# Controller_Board.net
KiCad netlist of a schematic drawn in EAGLE
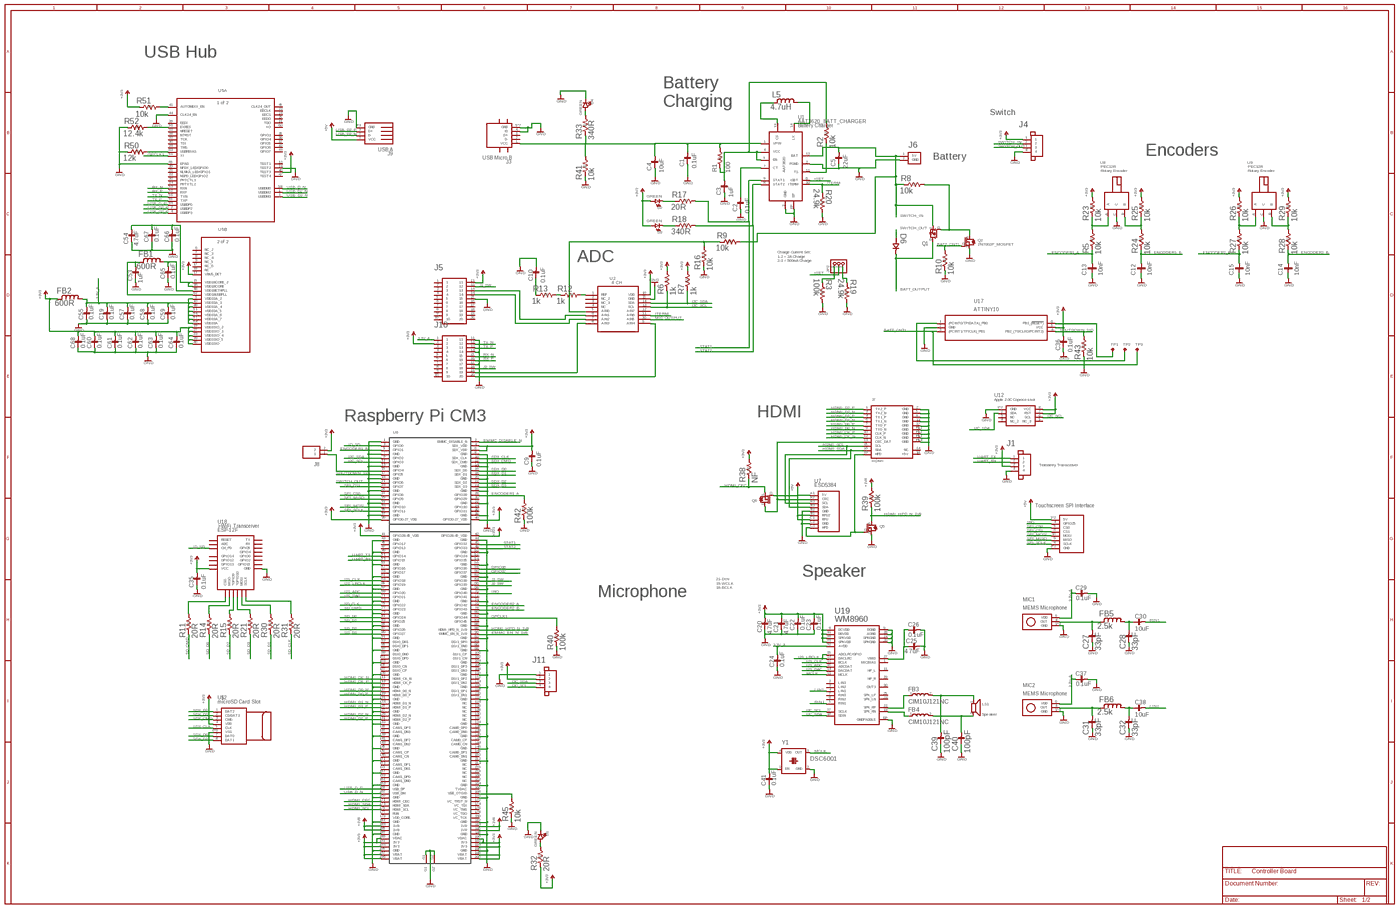
[diagram p0: schematic, sheet 1, overview]
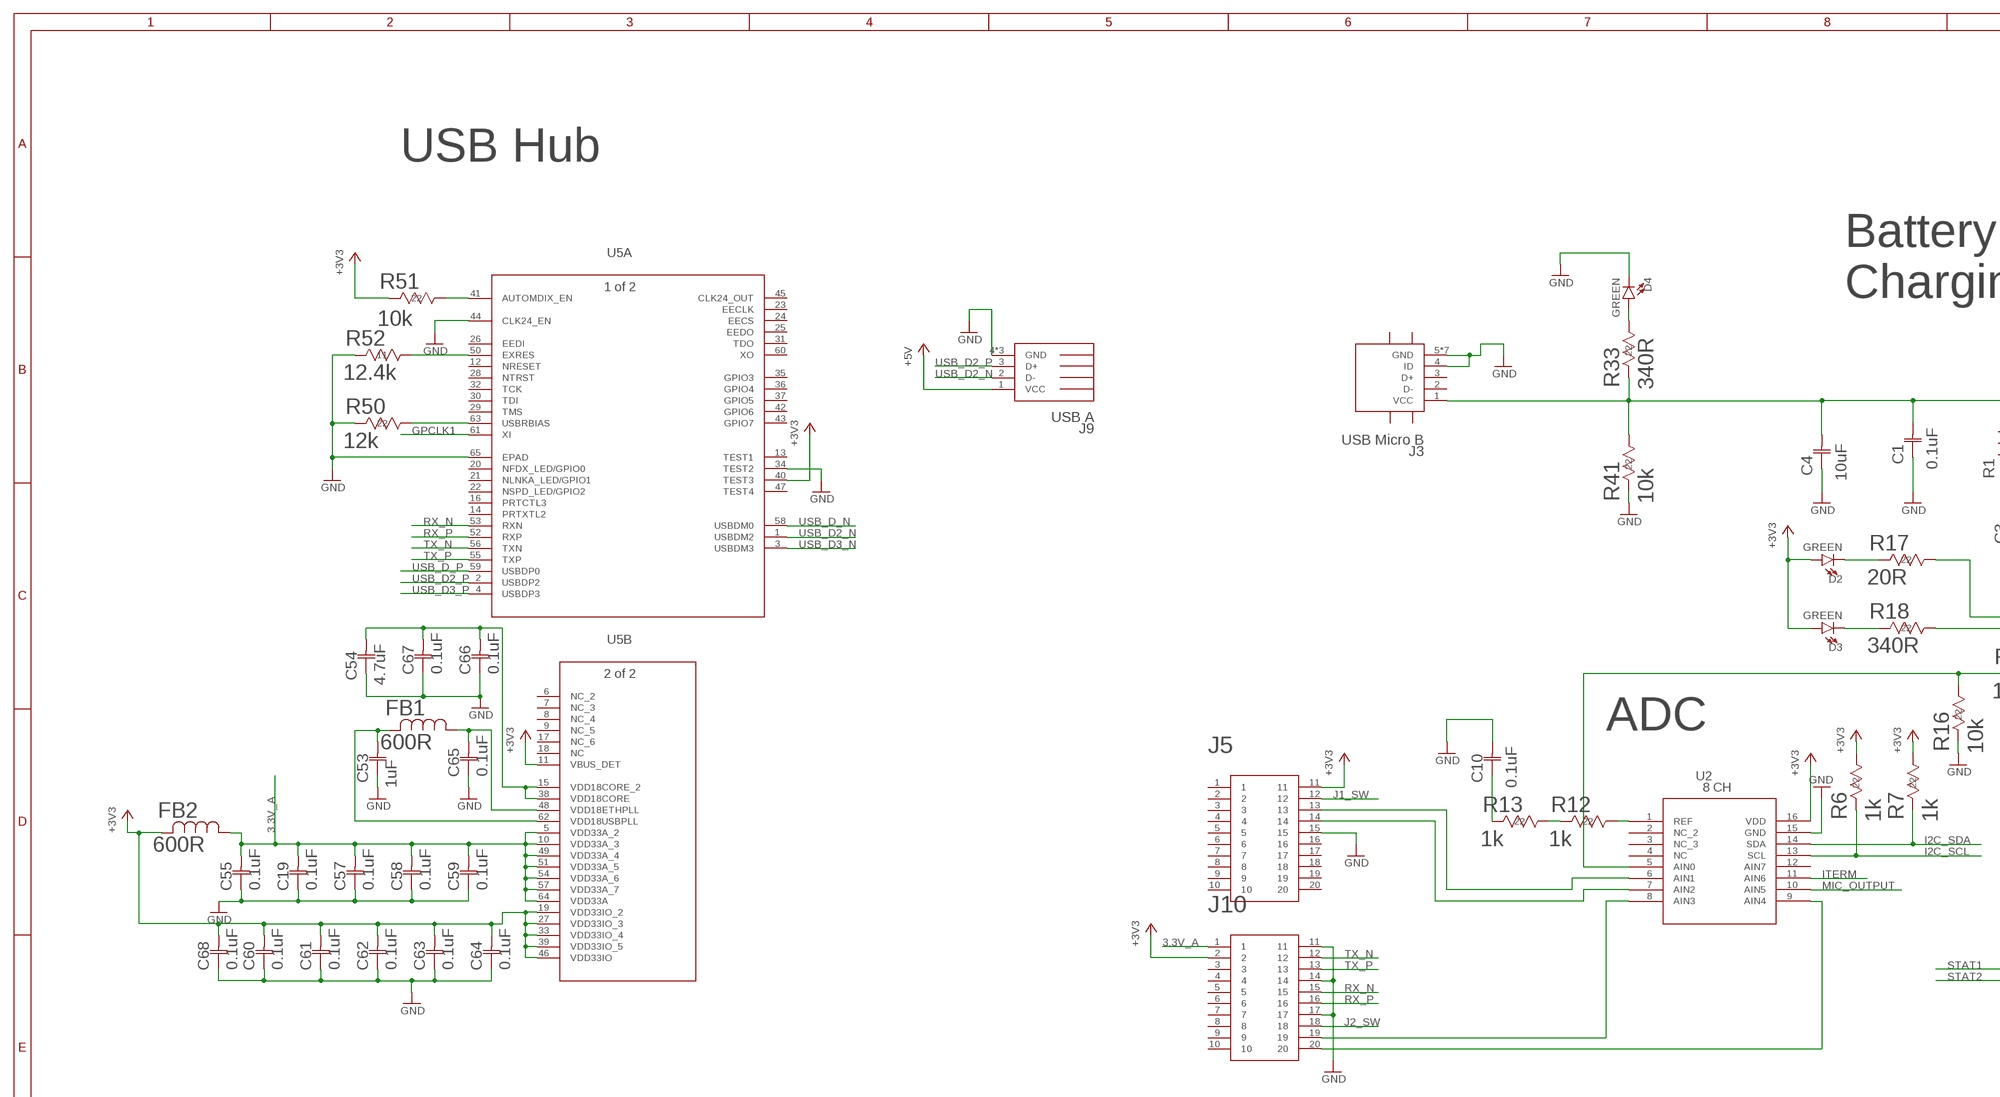
[diagram p1: schematic, sheet 1, part 1 of 4]
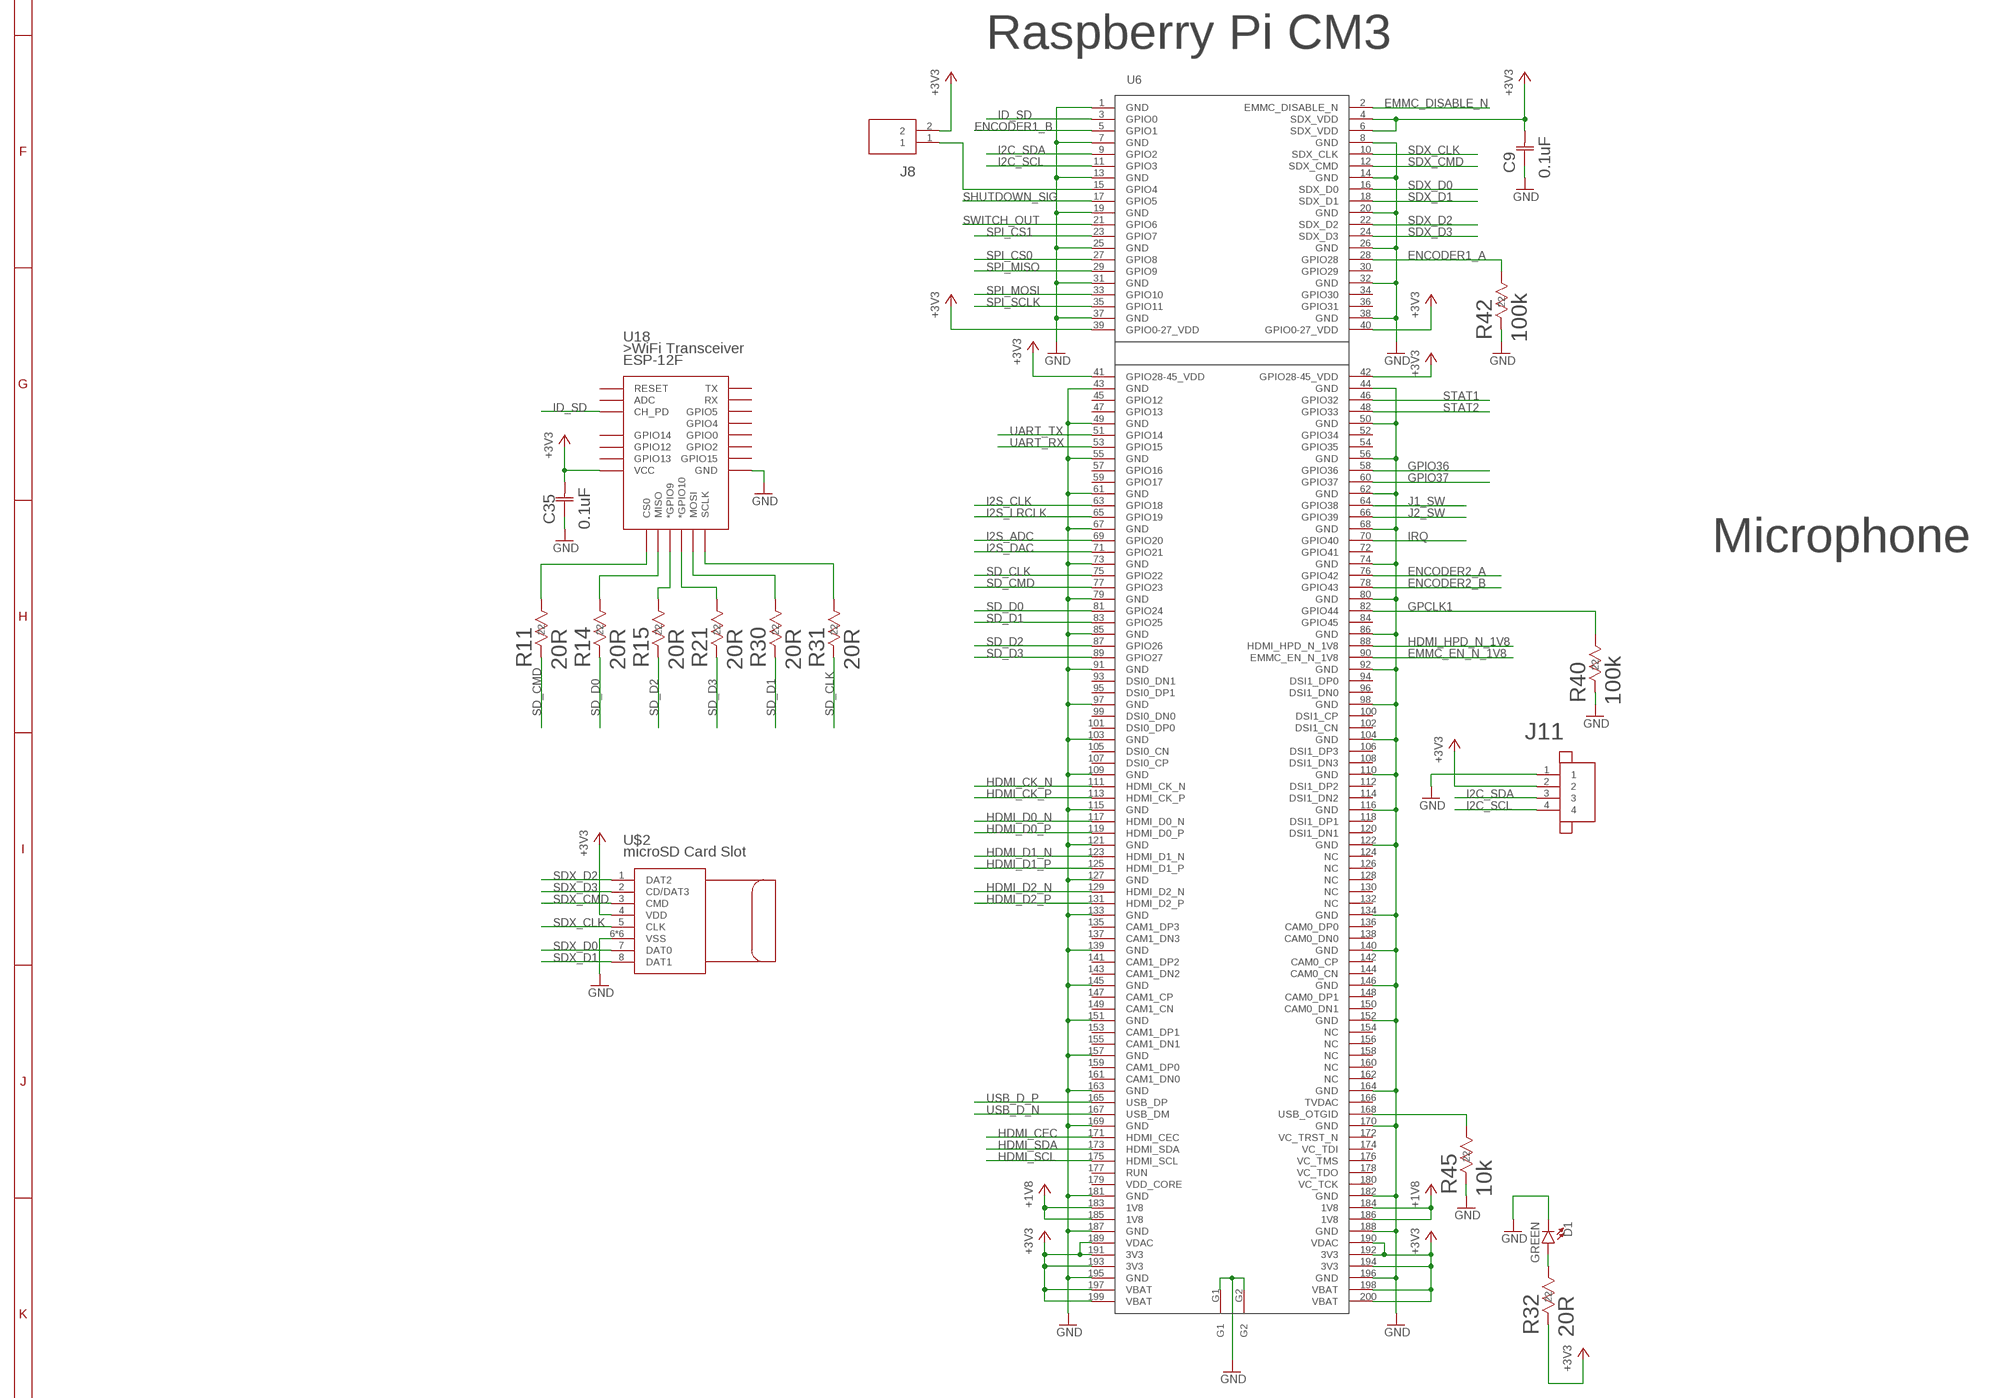
[diagram p2: schematic, sheet 1, part 2 of 4]
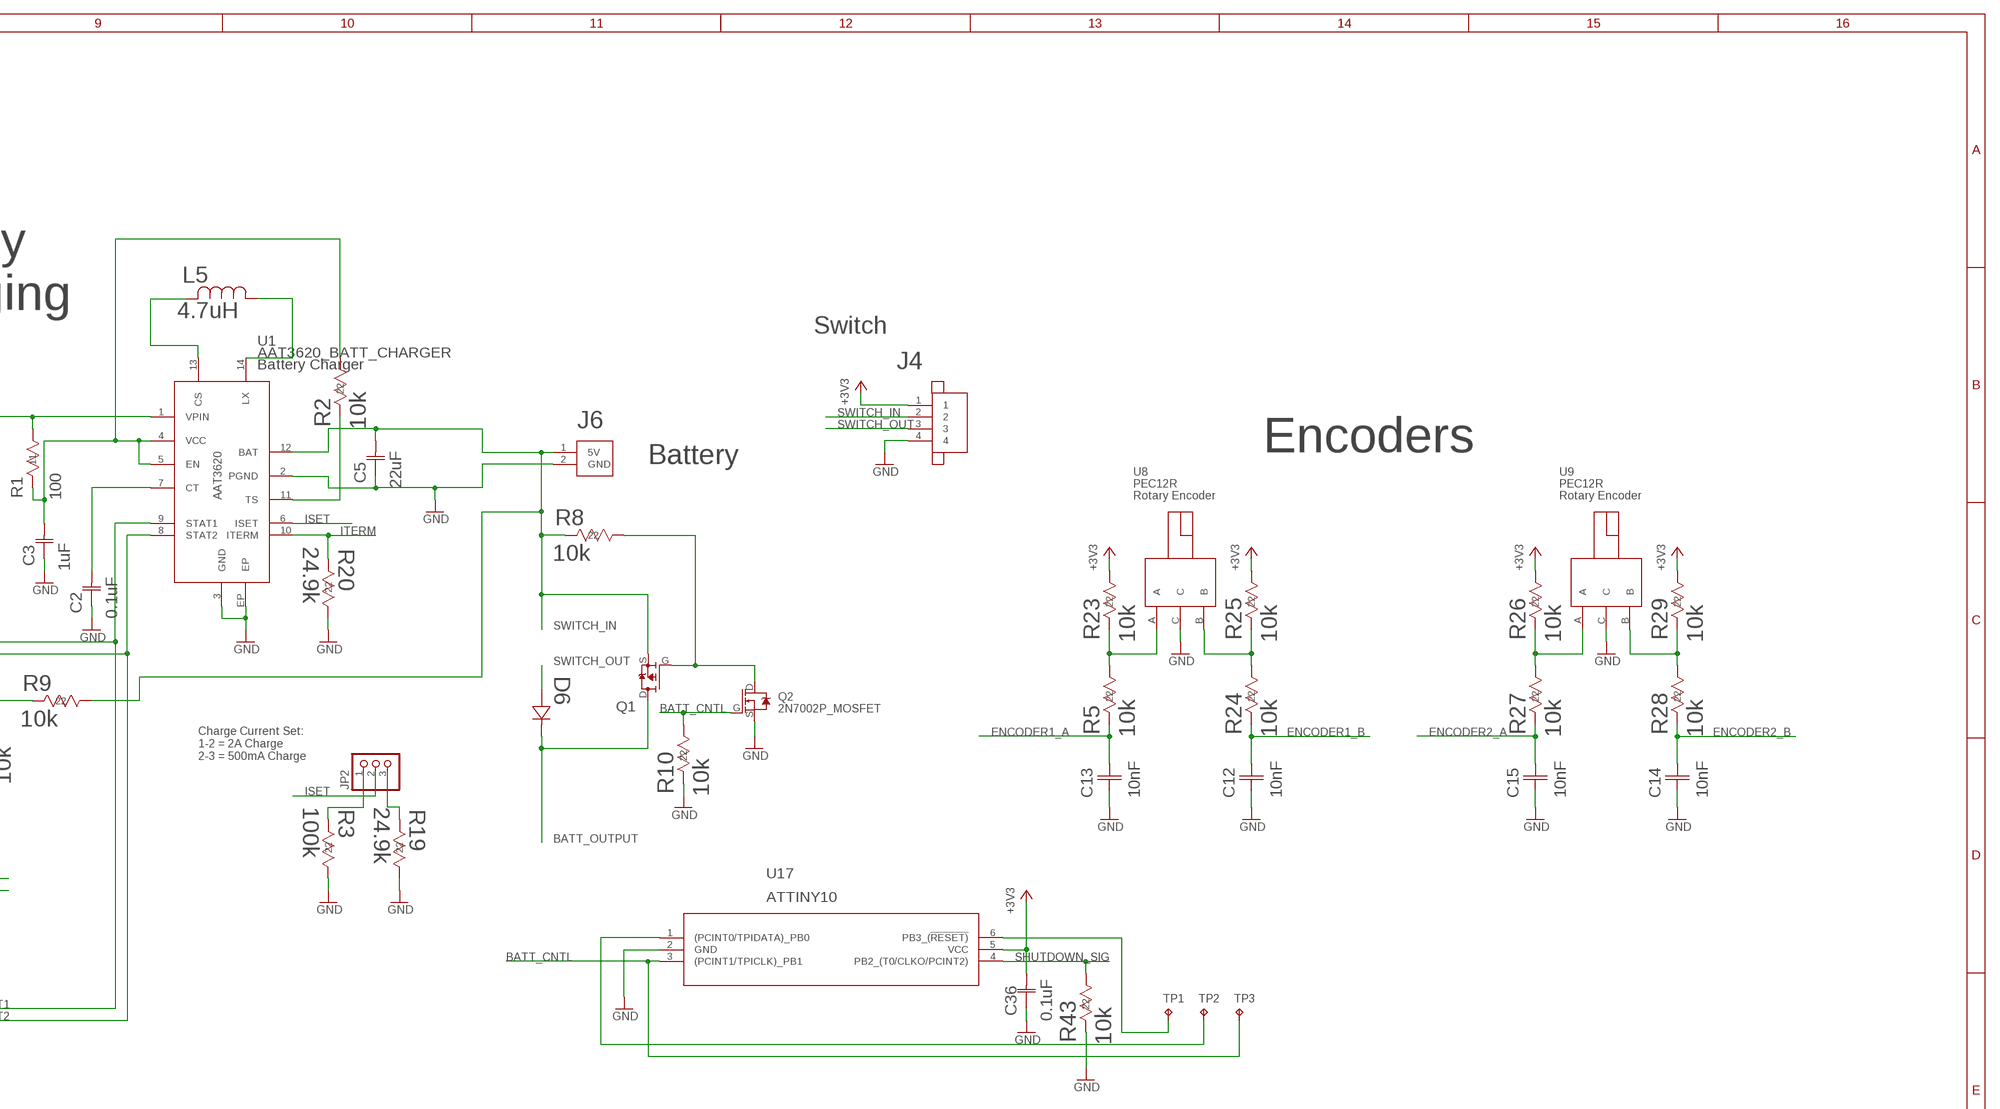
[diagram p3: schematic, sheet 1, part 3 of 4]
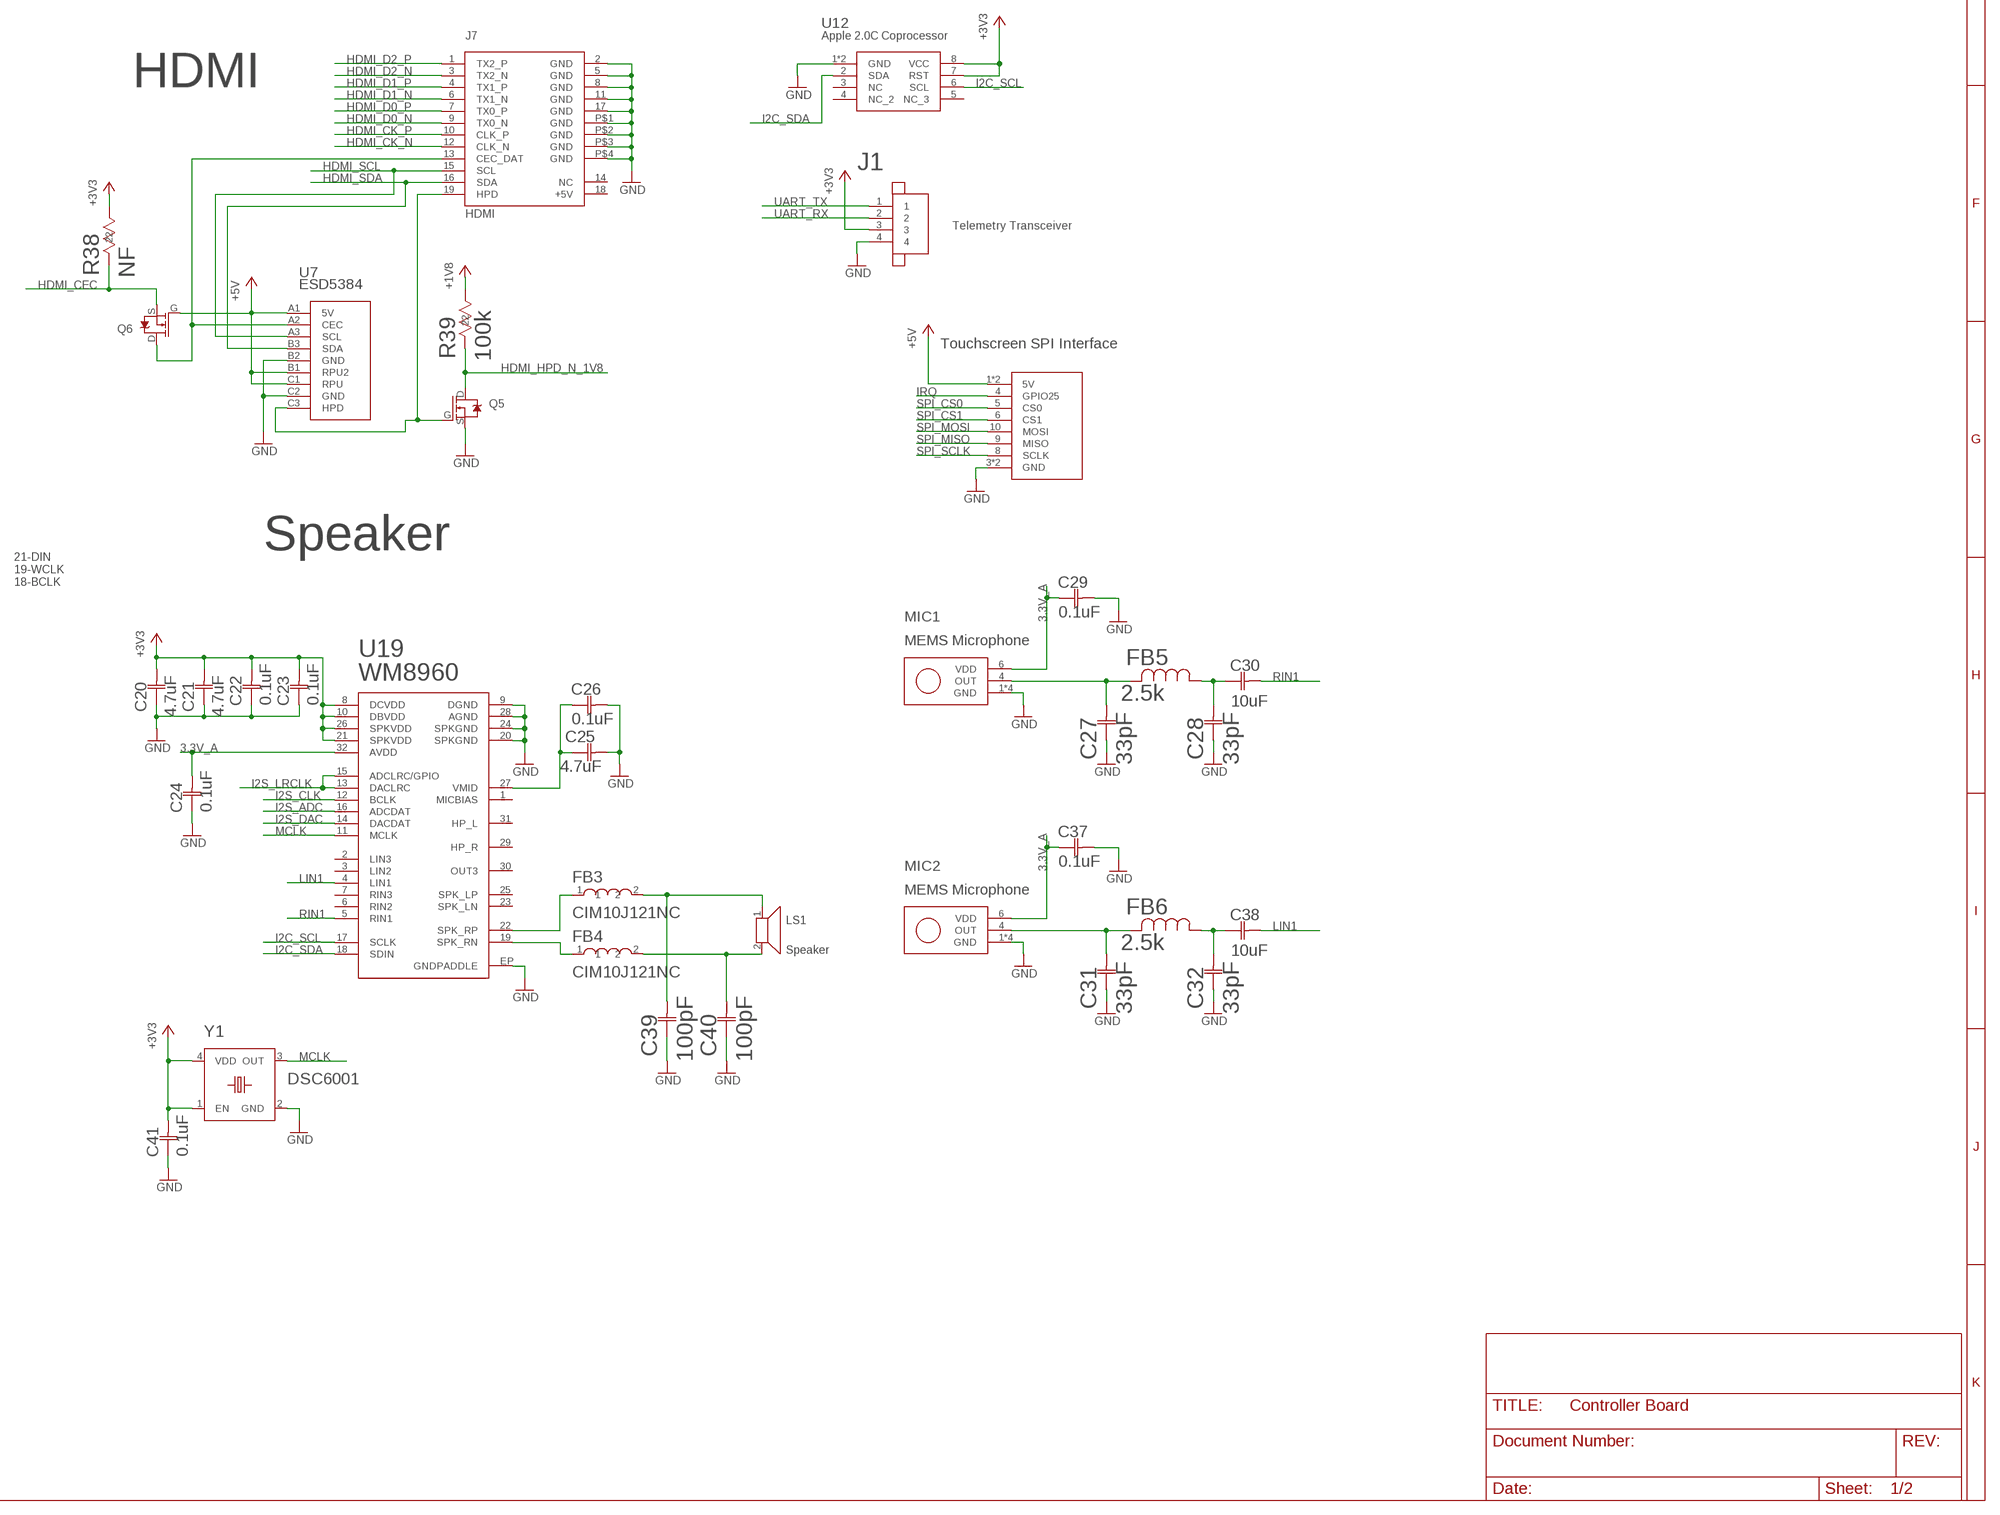
[diagram p4: schematic, sheet 1, part 4 of 4]
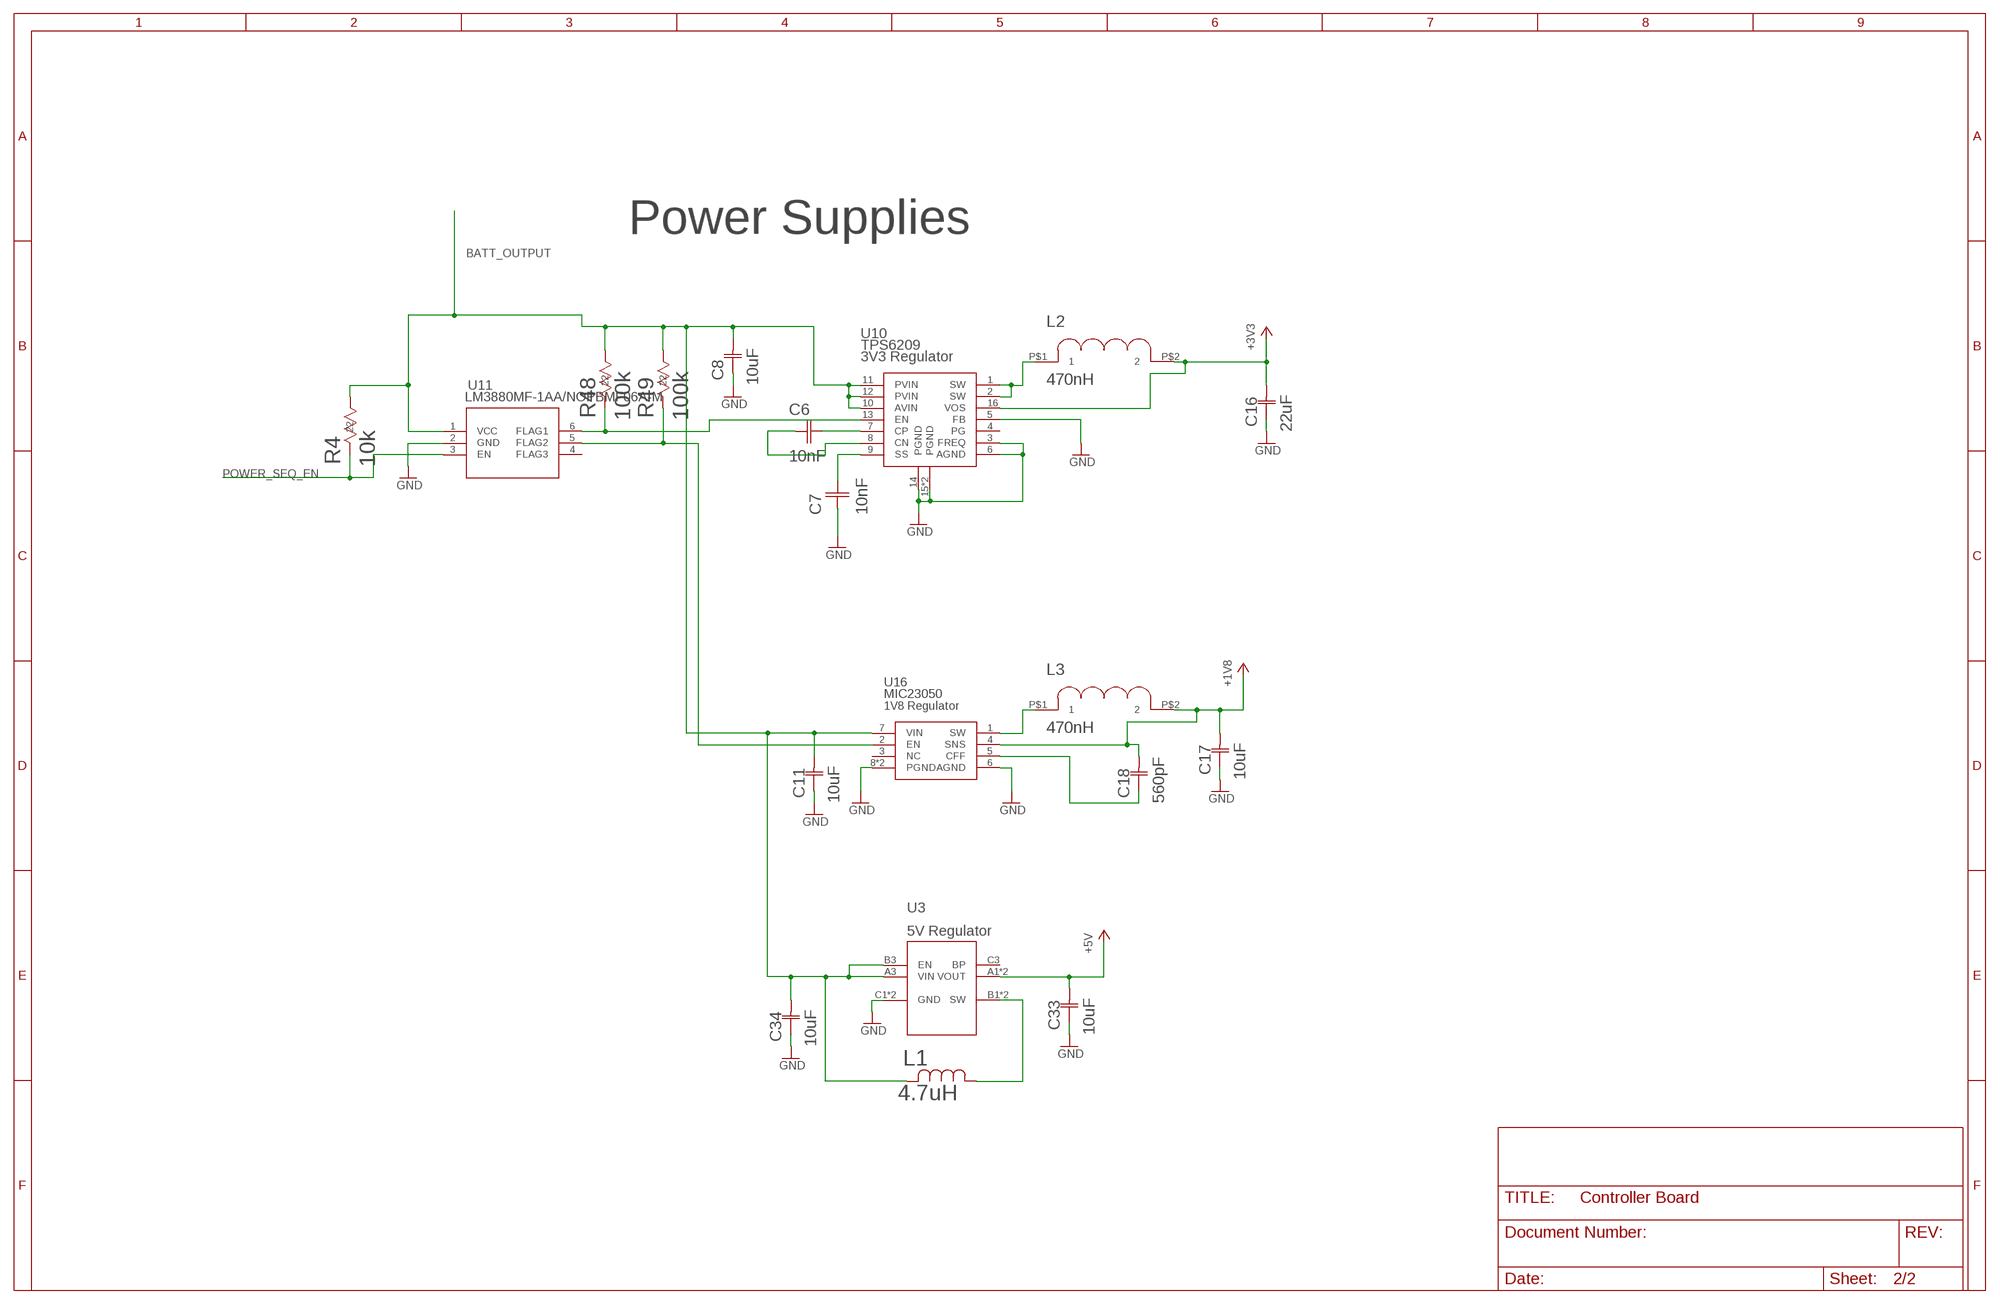
[diagram p5: schematic, sheet 2]

(export (version "E")
  (design (tool "Eeschema 10.0.6"))
  (components
    (comp (ref "C6")
      (value "10nF")
      (footprint "eagle-import:0603_CAPACITOR")
      (libsource (lib "eagle-import") (part "10NF_CAPACITOR"))
    )
    (comp (ref "C7")
      (value "10nF")
      (footprint "eagle-import:0603_CAPACITOR")
      (libsource (lib "eagle-import") (part "10NF_CAPACITOR"))
    )
    (comp (ref "C8")
      (value "10uF")
      (footprint "eagle-import:G-21")
      (fields
        (field (name "MANUFACTURER_PART_NUMBER") "GRM21BR60J106ME19L")
        (field (name "COPYRIGHT") "Copyright C 2015 Accelerated Designs. All rights reserved")
      )
      (libsource (lib "eagle-import") (part "Controller Board_178037_GRM21BR60J106ME19L"))
    )
    (comp (ref "C11")
      (value "10uF")
      (footprint "eagle-import:G-21")
      (fields
        (field (name "MANUFACTURER_PART_NUMBER") "GRM21BR60J106ME19L")
        (field (name "COPYRIGHT") "Copyright C 2015 Accelerated Designs. All rights reserved")
      )
      (libsource (lib "eagle-import") (part "Controller Board_178037_GRM21BR60J106ME19L"))
    )
    (comp (ref "C16")
      (value "22uF")
      (footprint "eagle-import:G-21")
      (fields
        (field (name "MANUFACTURER_PART_NUMBER") "GRM21BR60J226ME39L")
        (field (name "COPYRIGHT") "Copyright C 2015 Accelerated Designs. All rights reserved")
      )
      (libsource (lib "eagle-import") (part "GRM21BR60J226ME39L"))
    )
    (comp (ref "C17")
      (value "10uF")
      (footprint "eagle-import:G-21")
      (fields
        (field (name "MANUFACTURER_PART_NUMBER") "GRM21BR60J106ME19L")
        (field (name "COPYRIGHT") "Copyright C 2015 Accelerated Designs. All rights reserved")
      )
      (libsource (lib "eagle-import") (part "Controller Board_178037_GRM21BR60J106ME19L"))
    )
    (comp (ref "C18")
      (value "560pF")
      (footprint "eagle-import:CC0402N-M")
      (fields (field (name "MANUFACTURER_PART_NUMBER") "CC0402KRX7R9BB561"))
      (libsource (lib "eagle-import") (part "CC0402KRX7R9BB561CC0402N-M"))
    )
    (comp (ref "C33")
      (value "10uF")
      (footprint "eagle-import:G-21")
      (fields
        (field (name "MANUFACTURER_PART_NUMBER") "GRM21BR60J106ME19L")
        (field (name "COPYRIGHT") "Copyright C 2015 Accelerated Designs. All rights reserved")
      )
      (libsource (lib "eagle-import") (part "Controller Board_178037_GRM21BR60J106ME19L"))
    )
    (comp (ref "C34")
      (value "10uF")
      (footprint "eagle-import:G-21")
      (fields
        (field (name "MANUFACTURER_PART_NUMBER") "GRM21BR60J106ME19L")
        (field (name "COPYRIGHT") "Copyright C 2015 Accelerated Designs. All rights reserved")
      )
      (libsource (lib "eagle-import") (part "Controller Board_178037_GRM21BR60J106ME19L"))
    )
    (comp (ref "L1")
      (value "4.7uH")
      (footprint "eagle-import:1008")
      (libsource (lib "eagle-import") (part "DFE252012P-4R7M=P2{dblquote}"))
    )
    (comp (ref "L2")
      (value "470nH")
      (footprint "eagle-import:470NH_INDUCTOR")
      (libsource (lib "eagle-import") (part "470NH_INDUCTOR"))
    )
    (comp (ref "L3")
      (value "470nH")
      (footprint "eagle-import:470NH_INDUCTOR")
      (libsource (lib "eagle-import") (part "470NH_INDUCTOR"))
    )
    (comp (ref "R4")
      (value "10k")
      (footprint "eagle-import:RC0805N")
      (fields
        (field (name "DIGIKEYPARTNUMBER") "P10KDATRND")
        (field (name "MANUFACTURER_PART_NUMBER") "ERA6AEB103V")
        (field (name "TOLERANCE") "0.1%")
        (field (name "COPYRIGHT") "Copyright C 2015 Accelerated Designs. All rights reserved")
      )
      (libsource (lib "eagle-import") (part "Controller Board_178037_ERA-6AEB103V"))
    )
    (comp (ref "R48")
      (value "100k")
      (footprint "eagle-import:RC0603N-M")
      (fields (field (name "MANUFACTURER_PART_NUMBER") "RC0603JR07100KL"))
      (libsource (lib "eagle-import") (part "RC0603JR-07100KLRC0603N-M"))
    )
    (comp (ref "R49")
      (value "100k")
      (footprint "eagle-import:RC0603N-M")
      (fields (field (name "MANUFACTURER_PART_NUMBER") "RC0603JR07100KL"))
      (libsource (lib "eagle-import") (part "RC0603JR-07100KLRC0603N-M"))
    )
    (comp (ref "U3")
      (value "TPS61256YFFR")
      (footprint "eagle-import:YFF9")
      (libsource (lib "eagle-import") (part "TPS61256YFFR"))
    )
    (comp (ref "U10")
      (value "TPS6209")
      (footprint "eagle-import:VQFN16")
      (libsource (lib "eagle-import") (part "TPS6209"))
    )
    (comp (ref "U11")
      (value "LM3880MF-1AA/NOPBMF06A-M")
      (footprint "eagle-import:MF06A-M")
      (fields (field (name "MANUFACTURER_PART_NUMBER") "lm3880mf1aaNOPB"))
      (libsource (lib "eagle-import") (part "LM3880MF-1AA/NOPBMF06A-M"))
    )
    (comp (ref "U16")
      (value "MIC23050")
      (footprint "eagle-import:MLF(ML)_8PIN")
      (libsource (lib "eagle-import") (part "MIC23050"))
    )
    (comp (ref "C1")
      (value "0.1uF")
      (footprint "eagle-import:0805")
      (fields
        (field (name "MANUFACTURER_PART_NUMBER") "08055C104KAT2A")
        (field (name "COPYRIGHT") "Copyright C 2015 Accelerated Designs. All rights reserved")
      )
      (libsource (lib "eagle-import") (part "08055C104KAT2A"))
    )
    (comp (ref "C2")
      (value "0.1uF")
      (footprint "eagle-import:0805")
      (fields
        (field (name "MANUFACTURER_PART_NUMBER") "08055C104KAT2A")
        (field (name "COPYRIGHT") "Copyright C 2015 Accelerated Designs. All rights reserved")
      )
      (libsource (lib "eagle-import") (part "08055C104KAT2A"))
    )
    (comp (ref "C3")
      (value "1uF")
      (footprint "eagle-import:YAG_CC0805")
      (fields
        (field (name "MANUFACTURER_PART_NUMBER") "CC0805KKX7R7BB105")
        (field (name "COPYRIGHT") "Copyright C 2015 Accelerated Designs. All rights reserved")
      )
      (libsource (lib "eagle-import") (part "Controller Board_178037_CC0805KKX7R7BB105"))
    )
    (comp (ref "C4")
      (value "10uF")
      (footprint "eagle-import:G-21")
      (fields
        (field (name "MANUFACTURER_PART_NUMBER") "GRM21BR60J106ME19L")
        (field (name "COPYRIGHT") "Copyright C 2015 Accelerated Designs. All rights reserved")
      )
      (libsource (lib "eagle-import") (part "Controller Board_178037_GRM21BR60J106ME19L"))
    )
    (comp (ref "C5")
      (value "22uF")
      (footprint "eagle-import:G-21")
      (fields
        (field (name "MANUFACTURER_PART_NUMBER") "GRM21BR60J226ME39L")
        (field (name "COPYRIGHT") "Copyright C 2015 Accelerated Designs. All rights reserved")
      )
      (libsource (lib "eagle-import") (part "GRM21BR60J226ME39L"))
    )
    (comp (ref "C9")
      (value "0.1uF")
      (footprint "eagle-import:0805")
      (fields
        (field (name "MANUFACTURER_PART_NUMBER") "08055C104KAT2A")
        (field (name "COPYRIGHT") "Copyright C 2015 Accelerated Designs. All rights reserved")
      )
      (libsource (lib "eagle-import") (part "08055C104KAT2A"))
    )
    (comp (ref "C10")
      (value "0.1uF")
      (footprint "eagle-import:0805")
      (fields
        (field (name "MANUFACTURER_PART_NUMBER") "08055C104KAT2A")
        (field (name "COPYRIGHT") "Copyright C 2015 Accelerated Designs. All rights reserved")
      )
      (libsource (lib "eagle-import") (part "08055C104KAT2A"))
    )
    (comp (ref "C12")
      (value "10nF")
      (footprint "eagle-import:0603_CAPACITOR")
      (libsource (lib "eagle-import") (part "10NF_CAPACITOR"))
    )
    (comp (ref "C13")
      (value "10nF")
      (footprint "eagle-import:0603_CAPACITOR")
      (libsource (lib "eagle-import") (part "10NF_CAPACITOR"))
    )
    (comp (ref "C14")
      (value "10nF")
      (footprint "eagle-import:0603_CAPACITOR")
      (libsource (lib "eagle-import") (part "10NF_CAPACITOR"))
    )
    (comp (ref "C15")
      (value "10nF")
      (footprint "eagle-import:0603_CAPACITOR")
      (libsource (lib "eagle-import") (part "10NF_CAPACITOR"))
    )
    (comp (ref "C19")
      (value "0.1uF")
      (footprint "eagle-import:0402-M")
      (fields (field (name "MANUFACTURER_PART_NUMBER") "0402ZD104KAT2A"))
      (libsource (lib "eagle-import") (part "0402ZD104KAT2A0402-M"))
    )
    (comp (ref "C20")
      (value "4.7uF")
      (footprint "eagle-import:0603-M")
      (fields (field (name "MANUFACTURER_PART_NUMBER") "06036D475KAT2A"))
      (libsource (lib "eagle-import") (part "06036D475KAT2A0603-M"))
    )
    (comp (ref "C21")
      (value "4.7uF")
      (footprint "eagle-import:0603-M")
      (fields (field (name "MANUFACTURER_PART_NUMBER") "06036D475KAT2A"))
      (libsource (lib "eagle-import") (part "06036D475KAT2A0603-M"))
    )
    (comp (ref "C22")
      (value "0.1uF")
      (footprint "eagle-import:0402-M")
      (fields (field (name "MANUFACTURER_PART_NUMBER") "0402ZD104KAT2A"))
      (libsource (lib "eagle-import") (part "0402ZD104KAT2A0402-M"))
    )
    (comp (ref "C23")
      (value "0.1uF")
      (footprint "eagle-import:0402-M")
      (fields (field (name "MANUFACTURER_PART_NUMBER") "0402ZD104KAT2A"))
      (libsource (lib "eagle-import") (part "0402ZD104KAT2A0402-M"))
    )
    (comp (ref "C24")
      (value "0.1uF")
      (footprint "eagle-import:0402-M")
      (fields (field (name "MANUFACTURER_PART_NUMBER") "0402ZD104KAT2A"))
      (libsource (lib "eagle-import") (part "0402ZD104KAT2A0402-M"))
    )
    (comp (ref "C25")
      (value "4.7uF")
      (footprint "eagle-import:0603-M")
      (fields (field (name "MANUFACTURER_PART_NUMBER") "06036D475KAT2A"))
      (libsource (lib "eagle-import") (part "06036D475KAT2A0603-M"))
    )
    (comp (ref "C26")
      (value "0.1uF")
      (footprint "eagle-import:0402-M")
      (fields (field (name "MANUFACTURER_PART_NUMBER") "0402ZD104KAT2A"))
      (libsource (lib "eagle-import") (part "0402ZD104KAT2A0402-M"))
    )
    (comp (ref "C27")
      (value "33pF")
      (footprint "eagle-import:G-155-M")
      (fields (field (name "MANUFACTURER_PART_NUMBER") "GRM1555C1H330JA01D"))
      (libsource (lib "eagle-import") (part "GRM1555C1H330JA01DG-155-M"))
    )
    (comp (ref "C28")
      (value "33pF")
      (footprint "eagle-import:G-155-M")
      (fields (field (name "MANUFACTURER_PART_NUMBER") "GRM1555C1H330JA01D"))
      (libsource (lib "eagle-import") (part "GRM1555C1H330JA01DG-155-M"))
    )
    (comp (ref "C29")
      (value "0.1uF")
      (footprint "eagle-import:0402-M")
      (fields (field (name "MANUFACTURER_PART_NUMBER") "0402ZD104KAT2A"))
      (libsource (lib "eagle-import") (part "0402ZD104KAT2A0402-M"))
    )
    (comp (ref "C30")
      (value "10uF")
      (footprint "eagle-import:G-21")
      (fields
        (field (name "MANUFACTURER_PART_NUMBER") "GRM21BR60J106ME19L")
        (field (name "COPYRIGHT") "Copyright C 2015 Accelerated Designs. All rights reserved")
      )
      (libsource (lib "eagle-import") (part "GRM21BR60J106ME19L"))
    )
    (comp (ref "C31")
      (value "33pF")
      (footprint "eagle-import:G-155-M")
      (fields (field (name "MANUFACTURER_PART_NUMBER") "GRM1555C1H330JA01D"))
      (libsource (lib "eagle-import") (part "GRM1555C1H330JA01DG-155-M"))
    )
    (comp (ref "C32")
      (value "33pF")
      (footprint "eagle-import:G-155-M")
      (fields (field (name "MANUFACTURER_PART_NUMBER") "GRM1555C1H330JA01D"))
      (libsource (lib "eagle-import") (part "GRM1555C1H330JA01DG-155-M"))
    )
    (comp (ref "C35")
      (value "0.1uF")
      (footprint "eagle-import:0805")
      (fields
        (field (name "MANUFACTURER_PART_NUMBER") "08055C104KAT2A")
        (field (name "COPYRIGHT") "Copyright C 2015 Accelerated Designs. All rights reserved")
      )
      (libsource (lib "eagle-import") (part "08055C104KAT2A"))
    )
    (comp (ref "C36")
      (value "0.1uF")
      (footprint "eagle-import:0805")
      (fields
        (field (name "MANUFACTURER_PART_NUMBER") "08055C104KAT2A")
        (field (name "COPYRIGHT") "Copyright C 2015 Accelerated Designs. All rights reserved")
      )
      (libsource (lib "eagle-import") (part "08055C104KAT2A"))
    )
    (comp (ref "C37")
      (value "0.1uF")
      (footprint "eagle-import:0402-M")
      (fields (field (name "MANUFACTURER_PART_NUMBER") "0402ZD104KAT2A"))
      (libsource (lib "eagle-import") (part "0402ZD104KAT2A0402-M"))
    )
    (comp (ref "C38")
      (value "10uF")
      (footprint "eagle-import:G-21")
      (fields
        (field (name "MANUFACTURER_PART_NUMBER") "GRM21BR60J106ME19L")
        (field (name "COPYRIGHT") "Copyright C 2015 Accelerated Designs. All rights reserved")
      )
      (libsource (lib "eagle-import") (part "GRM21BR60J106ME19L"))
    )
    (comp (ref "C39")
      (value "100pF")
      (footprint "eagle-import:YAG_CC0402-M")
      (fields (field (name "MANUFACTURER_PART_NUMBER") "CC0402KRX7R9BB101"))
      (libsource (lib "eagle-import") (part "CC0402KRX7R9BB101YAG_CC0402-M"))
    )
    (comp (ref "C40")
      (value "100pF")
      (footprint "eagle-import:YAG_CC0402-M")
      (fields (field (name "MANUFACTURER_PART_NUMBER") "CC0402KRX7R9BB101"))
      (libsource (lib "eagle-import") (part "CC0402KRX7R9BB101YAG_CC0402-M"))
    )
    (comp (ref "C41")
      (value "0.1uF")
      (footprint "eagle-import:0402-M")
      (fields (field (name "MANUFACTURER_PART_NUMBER") "0402ZD104KAT2A"))
      (libsource (lib "eagle-import") (part "0402ZD104KAT2A0402-M"))
    )
    (comp (ref "C53")
      (value "1uF")
      (footprint "eagle-import:YAG_CC0805")
      (fields
        (field (name "MANUFACTURER_PART_NUMBER") "CC0805KKX7R7BB105")
        (field (name "COPYRIGHT") "Copyright C 2015 Accelerated Designs. All rights reserved")
      )
      (libsource (lib "eagle-import") (part "CC0805KKX7R7BB105"))
    )
    (comp (ref "C54")
      (value "4.7uF")
      (footprint "eagle-import:0603-M")
      (fields (field (name "MANUFACTURER_PART_NUMBER") "06036D475KAT2A"))
      (libsource (lib "eagle-import") (part "06036D475KAT2A0603-M"))
    )
    (comp (ref "C55")
      (value "0.1uF")
      (footprint "eagle-import:0402-M")
      (fields (field (name "MANUFACTURER_PART_NUMBER") "0402ZD104KAT2A"))
      (libsource (lib "eagle-import") (part "0402ZD104KAT2A0402-M"))
    )
    (comp (ref "C57")
      (value "0.1uF")
      (footprint "eagle-import:0402-M")
      (fields (field (name "MANUFACTURER_PART_NUMBER") "0402ZD104KAT2A"))
      (libsource (lib "eagle-import") (part "0402ZD104KAT2A0402-M"))
    )
    (comp (ref "C58")
      (value "0.1uF")
      (footprint "eagle-import:0402-M")
      (fields (field (name "MANUFACTURER_PART_NUMBER") "0402ZD104KAT2A"))
      (libsource (lib "eagle-import") (part "0402ZD104KAT2A0402-M"))
    )
    (comp (ref "C59")
      (value "0.1uF")
      (footprint "eagle-import:0402-M")
      (fields (field (name "MANUFACTURER_PART_NUMBER") "0402ZD104KAT2A"))
      (libsource (lib "eagle-import") (part "0402ZD104KAT2A0402-M"))
    )
    (comp (ref "C60")
      (value "0.1uF")
      (footprint "eagle-import:0402-M")
      (fields (field (name "MANUFACTURER_PART_NUMBER") "0402ZD104KAT2A"))
      (libsource (lib "eagle-import") (part "0402ZD104KAT2A0402-M"))
    )
    (comp (ref "C61")
      (value "0.1uF")
      (footprint "eagle-import:0402-M")
      (fields (field (name "MANUFACTURER_PART_NUMBER") "0402ZD104KAT2A"))
      (libsource (lib "eagle-import") (part "0402ZD104KAT2A0402-M"))
    )
    (comp (ref "C62")
      (value "0.1uF")
      (footprint "eagle-import:0402-M")
      (fields (field (name "MANUFACTURER_PART_NUMBER") "0402ZD104KAT2A"))
      (libsource (lib "eagle-import") (part "0402ZD104KAT2A0402-M"))
    )
    (comp (ref "C63")
      (value "0.1uF")
      (footprint "eagle-import:0402-M")
      (fields (field (name "MANUFACTURER_PART_NUMBER") "0402ZD104KAT2A"))
      (libsource (lib "eagle-import") (part "0402ZD104KAT2A0402-M"))
    )
    (comp (ref "C64")
      (value "0.1uF")
      (footprint "eagle-import:0402-M")
      (fields (field (name "MANUFACTURER_PART_NUMBER") "0402ZD104KAT2A"))
      (libsource (lib "eagle-import") (part "0402ZD104KAT2A0402-M"))
    )
    (comp (ref "C65")
      (value "0.1uF")
      (footprint "eagle-import:0402-M")
      (fields (field (name "MANUFACTURER_PART_NUMBER") "0402ZD104KAT2A"))
      (libsource (lib "eagle-import") (part "0402ZD104KAT2A0402-M"))
    )
    (comp (ref "C66")
      (value "0.1uF")
      (footprint "eagle-import:0402-M")
      (fields (field (name "MANUFACTURER_PART_NUMBER") "0402ZD104KAT2A"))
      (libsource (lib "eagle-import") (part "0402ZD104KAT2A0402-M"))
    )
    (comp (ref "C67")
      (value "0.1uF")
      (footprint "eagle-import:0402-M")
      (fields (field (name "MANUFACTURER_PART_NUMBER") "0402ZD104KAT2A"))
      (libsource (lib "eagle-import") (part "0402ZD104KAT2A0402-M"))
    )
    (comp (ref "C68")
      (value "0.1uF")
      (footprint "eagle-import:0402-M")
      (fields (field (name "MANUFACTURER_PART_NUMBER") "0402ZD104KAT2A"))
      (libsource (lib "eagle-import") (part "0402ZD104KAT2A0402-M"))
    )
    (comp (ref "D1")
      (value "GREEN")
      (footprint "eagle-import:LED-0603")
      (libsource (lib "eagle-import") (part "LED-GREEN0603"))
    )
    (comp (ref "D2")
      (value "GREEN")
      (footprint "eagle-import:LED-0603")
      (libsource (lib "eagle-import") (part "LED-GREEN0603"))
    )
    (comp (ref "D3")
      (value "GREEN")
      (footprint "eagle-import:LED-0603")
      (libsource (lib "eagle-import") (part "LED-GREEN0603"))
    )
    (comp (ref "D4")
      (value "GREEN")
      (footprint "eagle-import:LED-0603")
      (libsource (lib "eagle-import") (part "LED-GREEN0603"))
    )
    (comp (ref "D6")
      (value "1N4148W-7-FSOD123-M")
      (footprint "eagle-import:SOD123-M")
      (fields
        (field (name "MANUFACTURER_PART_NUMBER") "1N4148W7F")
        (field (name "COPYRIGHT") "Copyright C 2015 Accelerated Designs. All rights reserved")
      )
      (libsource (lib "eagle-import") (part "1N4148W-7-FSOD123-M"))
    )
    (comp (ref "FB1")
      (value "600R")
      (footprint "eagle-import:IND_BLM18_0603-M")
      (fields (field (name "MANUFACTURER_PART_NUMBER") "BLM18AG601SN1D"))
      (libsource (lib "eagle-import") (part "BLM18AG601SN1DIND_BLM18_0603-M"))
    )
    (comp (ref "FB2")
      (value "600R")
      (footprint "eagle-import:IND_BLM18_0603-M")
      (fields (field (name "MANUFACTURER_PART_NUMBER") "BLM18AG601SN1D"))
      (libsource (lib "eagle-import") (part "BLM18AG601SN1DIND_BLM18_0603-M"))
    )
    (comp (ref "FB3")
      (value "CIM10J121NC")
      (footprint "eagle-import:0603_CAPACITOR")
      (libsource (lib "eagle-import") (part "CIM10J121NC"))
    )
    (comp (ref "FB4")
      (value "CIM10J121NC")
      (footprint "eagle-import:0603_CAPACITOR")
      (libsource (lib "eagle-import") (part "CIM10J121NC"))
    )
    (comp (ref "FB5")
      (value "2.5k")
      (footprint "eagle-import:IND_BLM18_0603-M")
      (fields (field (name "MANUFACTURER_PART_NUMBER") "BLM18BD252SN1D"))
      (libsource (lib "eagle-import") (part "BLM18BD252SN1DIND_BLM18_0603-M"))
    )
    (comp (ref "FB6")
      (value "2.5k")
      (footprint "eagle-import:IND_BLM18_0603-M")
      (fields (field (name "MANUFACTURER_PART_NUMBER") "BLM18BD252SN1D"))
      (libsource (lib "eagle-import") (part "BLM18BD252SN1DIND_BLM18_0603-M"))
    )
    (comp (ref "J1")
      (value "JST_SH_4POS")
      (footprint "eagle-import:JST_SH_4POS")
      (libsource (lib "eagle-import") (part "JST_SH_4POS"))
    )
    (comp (ref "J2")
      (value "3.5_TOUCHSCREEN")
      (footprint "eagle-import:3.5_TOUCHSCREEN")
      (libsource (lib "eagle-import") (part "3.5_TOUCHSCREEN"))
    )
    (comp (ref "J3")
      (value "USB_MICRO_B_SMT")
      (footprint "eagle-import:USB_MICRO_B_SMT")
      (libsource (lib "eagle-import") (part "USB_MICRO_B_SMT"))
    )
    (comp (ref "J4")
      (value "JST_SH_4POS")
      (footprint "eagle-import:JST_SH_4POS")
      (libsource (lib "eagle-import") (part "JST_SH_4POS"))
    )
    (comp (ref "J5")
      (value "EDGE_CONNECTOR_20POS")
      (footprint "eagle-import:EDGE_CONNECTOR_20POS")
      (libsource (lib "eagle-import") (part "EDGE_CONNECTOR_20POS"))
    )
    (comp (ref "J6")
      (value "POWER_CONNECTOR")
      (footprint "eagle-import:XH_CONNECTOR")
      (libsource (lib "eagle-import") (part "POWER_CONNECTOR"))
    )
    (comp (ref "J7")
      (value "HDMI")
      (footprint "eagle-import:HDMI")
      (libsource (lib "eagle-import") (part "HDMI"))
    )
    (comp (ref "J8")
      (value "2_PIN_CONNECTOR")
      (footprint "eagle-import:XH_CONNECTOR")
      (libsource (lib "eagle-import") (part "2_PIN_CONNECTOR"))
    )
    (comp (ref "J9")
      (value "USB_A_RECEPT")
      (footprint "eagle-import:USB_A_RECEPT")
      (libsource (lib "eagle-import") (part "USB_A_RECEPT"))
    )
    (comp (ref "J10")
      (value "EDGE_CONNECTOR_20POS")
      (footprint "eagle-import:EDGE_CONNECTOR_20POS")
      (libsource (lib "eagle-import") (part "EDGE_CONNECTOR_20POS"))
    )
    (comp (ref "J11")
      (value "JST_SH_4POS")
      (footprint "eagle-import:JST_SH_4POS")
      (libsource (lib "eagle-import") (part "JST_SH_4POS"))
    )
    (comp (ref "JP2")
      (value "PINHD-1X3")
      (footprint "eagle-import:1X03")
      (libsource (lib "eagle-import") (part "PINHD-1X3"))
    )
    (comp (ref "L5")
      (value "4.7uH")
      (footprint "eagle-import:1008")
      (libsource (lib "eagle-import") (part "DFE252012P-4R7M=P2{dblquote}"))
    )
    (comp (ref "LS1")
      (value "SP-1510")
      (footprint "eagle-import:SPEAKER")
      (libsource (lib "eagle-import") (part "SP-1510"))
    )
    (comp (ref "MIC1")
      (value "SPH1642HT5H-1")
      (footprint "eagle-import:SISONIC_MICROPHONE")
      (libsource (lib "eagle-import") (part "SPH1642HT5H-1"))
    )
    (comp (ref "MIC2")
      (value "SPH1642HT5H-1")
      (footprint "eagle-import:SISONIC_MICROPHONE")
      (libsource (lib "eagle-import") (part "SPH1642HT5H-1"))
    )
    (comp (ref "Q1")
      (value "DMP3099L")
      (footprint "eagle-import:SOT-23_(TO-236AB)")
      (libsource (lib "eagle-import") (part "DMP3099L"))
    )
    (comp (ref "Q2")
      (value "2N7002P_MOSFET")
      (footprint "eagle-import:SOT-23_(TO-236AB)")
      (libsource (lib "eagle-import") (part "2N7002P_MOSFET"))
    )
    (comp (ref "Q5")
      (value "DMG1012T")
      (footprint "eagle-import:SOT-523")
      (libsource (lib "eagle-import") (part "DMG1012T"))
    )
    (comp (ref "Q6")
      (value "DMG1012T")
      (footprint "eagle-import:SOT-523")
      (libsource (lib "eagle-import") (part "DMG1012T"))
    )
    (comp (ref "R1")
      (value "100")
      (footprint "eagle-import:1206")
      (libsource (lib "eagle-import") (part "100_RESISTOR"))
    )
    (comp (ref "R2")
      (value "10k")
      (footprint "eagle-import:RC0805N")
      (fields
        (field (name "DIGIKEYPARTNUMBER") "P10KDATRND")
        (field (name "MANUFACTURER_PART_NUMBER") "ERA6AEB103V")
        (field (name "TOLERANCE") "0.1%")
        (field (name "COPYRIGHT") "Copyright C 2015 Accelerated Designs. All rights reserved")
      )
      (libsource (lib "eagle-import") (part "Controller Board_178037_ERA-6AEB103V"))
    )
    (comp (ref "R3")
      (value "100k")
      (footprint "eagle-import:RC0603N-M")
      (fields (field (name "MANUFACTURER_PART_NUMBER") "RC0603JR07100KL"))
      (libsource (lib "eagle-import") (part "RC0603JR-07100KLRC0603N-M"))
    )
    (comp (ref "R5")
      (value "10k")
      (footprint "eagle-import:RC0805N")
      (fields
        (field (name "DIGIKEYPARTNUMBER") "P10KDATRND")
        (field (name "MANUFACTURER_PART_NUMBER") "ERA6AEB103V")
        (field (name "TOLERANCE") "0.1%")
        (field (name "COPYRIGHT") "Copyright C 2015 Accelerated Designs. All rights reserved")
      )
      (libsource (lib "eagle-import") (part "Controller Board_178037_ERA-6AEB103V"))
    )
    (comp (ref "R6")
      (value "1k")
      (footprint "eagle-import:RC0603N-M")
      (fields
        (field (name "DIGIKEYPARTNUMBER") "3111.0KGRTRND")
        (field (name "MANUFACTURER_PART_NUMBER") "RC0603JR071KL")
        (field (name "NEWARKPARTNUMBER") "14M7231")
        (field (name "COPYRIGHT") "Copyright C 2015 Accelerated Designs. All rights reserved")
      )
      (libsource (lib "eagle-import") (part "RC0603JR-071KLRC0603N-M"))
    )
    (comp (ref "R7")
      (value "1k")
      (footprint "eagle-import:RC0603N-M")
      (fields
        (field (name "DIGIKEYPARTNUMBER") "3111.0KGRTRND")
        (field (name "MANUFACTURER_PART_NUMBER") "RC0603JR071KL")
        (field (name "NEWARKPARTNUMBER") "14M7231")
        (field (name "COPYRIGHT") "Copyright C 2015 Accelerated Designs. All rights reserved")
      )
      (libsource (lib "eagle-import") (part "RC0603JR-071KLRC0603N-M"))
    )
    (comp (ref "R8")
      (value "10k")
      (footprint "eagle-import:RC0805N")
      (fields
        (field (name "DIGIKEYPARTNUMBER") "P10KDATRND")
        (field (name "MANUFACTURER_PART_NUMBER") "ERA6AEB103V")
        (field (name "TOLERANCE") "0.1%")
        (field (name "COPYRIGHT") "Copyright C 2015 Accelerated Designs. All rights reserved")
      )
      (libsource (lib "eagle-import") (part "Controller Board_178037_ERA-6AEB103V"))
    )
    (comp (ref "R9")
      (value "10k")
      (footprint "eagle-import:RC0805N")
      (fields
        (field (name "DIGIKEYPARTNUMBER") "P10KDATRND")
        (field (name "MANUFACTURER_PART_NUMBER") "ERA6AEB103V")
        (field (name "TOLERANCE") "0.1%")
        (field (name "COPYRIGHT") "Copyright C 2015 Accelerated Designs. All rights reserved")
      )
      (libsource (lib "eagle-import") (part "Controller Board_178037_ERA-6AEB103V"))
    )
    (comp (ref "R10")
      (value "10k")
      (footprint "eagle-import:RC0805N")
      (fields
        (field (name "DIGIKEYPARTNUMBER") "P10KDATRND")
        (field (name "MANUFACTURER_PART_NUMBER") "ERA6AEB103V")
        (field (name "TOLERANCE") "0.1%")
        (field (name "COPYRIGHT") "Copyright C 2015 Accelerated Designs. All rights reserved")
      )
      (libsource (lib "eagle-import") (part "Controller Board_178037_ERA-6AEB103V"))
    )
    (comp (ref "R11")
      (value "20R")
      (footprint "eagle-import:RC0603N-M")
      (fields (field (name "MANUFACTURER_PART_NUMBER") "RC0603JR0720RL"))
      (libsource (lib "eagle-import") (part "RC0603JR-0720RLRC0603N-M"))
    )
    (comp (ref "R12")
      (value "1k")
      (footprint "eagle-import:RC0603N-M")
      (fields
        (field (name "DIGIKEYPARTNUMBER") "3111.0KGRTRND")
        (field (name "MANUFACTURER_PART_NUMBER") "RC0603JR071KL")
        (field (name "NEWARKPARTNUMBER") "14M7231")
        (field (name "COPYRIGHT") "Copyright C 2015 Accelerated Designs. All rights reserved")
      )
      (libsource (lib "eagle-import") (part "RC0603JR-071KLRC0603N-M"))
    )
    (comp (ref "R13")
      (value "1k")
      (footprint "eagle-import:RC0603N-M")
      (fields
        (field (name "DIGIKEYPARTNUMBER") "3111.0KGRTRND")
        (field (name "MANUFACTURER_PART_NUMBER") "RC0603JR071KL")
        (field (name "NEWARKPARTNUMBER") "14M7231")
        (field (name "COPYRIGHT") "Copyright C 2015 Accelerated Designs. All rights reserved")
      )
      (libsource (lib "eagle-import") (part "RC0603JR-071KLRC0603N-M"))
    )
    (comp (ref "R14")
      (value "20R")
      (footprint "eagle-import:RC0603N-M")
      (fields (field (name "MANUFACTURER_PART_NUMBER") "RC0603JR0720RL"))
      (libsource (lib "eagle-import") (part "RC0603JR-0720RLRC0603N-M"))
    )
    (comp (ref "R15")
      (value "20R")
      (footprint "eagle-import:RC0603N-M")
      (fields (field (name "MANUFACTURER_PART_NUMBER") "RC0603JR0720RL"))
      (libsource (lib "eagle-import") (part "RC0603JR-0720RLRC0603N-M"))
    )
    (comp (ref "R16")
      (value "10k")
      (footprint "eagle-import:RC0805N")
      (fields
        (field (name "DIGIKEYPARTNUMBER") "P10KDATRND")
        (field (name "MANUFACTURER_PART_NUMBER") "ERA6AEB103V")
        (field (name "TOLERANCE") "0.1%")
        (field (name "COPYRIGHT") "Copyright C 2015 Accelerated Designs. All rights reserved")
      )
      (libsource (lib "eagle-import") (part "Controller Board_178037_ERA-6AEB103V"))
    )
    (comp (ref "R17")
      (value "20R")
      (footprint "eagle-import:RC0603N-M")
      (fields (field (name "MANUFACTURER_PART_NUMBER") "RC0603JR0720RL"))
      (libsource (lib "eagle-import") (part "RC0603JR-0720RLRC0603N-M"))
    )
    (comp (ref "R18")
      (value "340R")
      (footprint "eagle-import:RC0603N")
      (fields
        (field (name "DIGIKEYPARTNUMBER") "311340HRTRND")
        (field (name "MANUFACTURER_PART_NUMBER") "RC0603FR07340RL")
        (field (name "NEWARKPARTNUMBER") "66R2325")
        (field (name "COPYRIGHT") "Copyright C 2015 Accelerated Designs. All rights reserved")
      )
      (libsource (lib "eagle-import") (part "RC0603FR-07340RL"))
    )
    (comp (ref "R19")
      (value "24.9k")
      (footprint "eagle-import:RC0402N-M")
      (fields (field (name "MANUFACTURER_PART_NUMBER") "RC0402FR0724K9L"))
      (libsource (lib "eagle-import") (part "RC0402FR-0724K9LRC0402N-M"))
    )
    (comp (ref "R20")
      (value "24.9k")
      (footprint "eagle-import:RC0402N-M")
      (fields (field (name "MANUFACTURER_PART_NUMBER") "RC0402FR0724K9L"))
      (libsource (lib "eagle-import") (part "RC0402FR-0724K9LRC0402N-M"))
    )
    (comp (ref "R21")
      (value "20R")
      (footprint "eagle-import:RC0603N-M")
      (fields (field (name "MANUFACTURER_PART_NUMBER") "RC0603JR0720RL"))
      (libsource (lib "eagle-import") (part "RC0603JR-0720RLRC0603N-M"))
    )
    (comp (ref "R23")
      (value "10k")
      (footprint "eagle-import:RC0805N")
      (fields
        (field (name "DIGIKEYPARTNUMBER") "P10KDATRND")
        (field (name "MANUFACTURER_PART_NUMBER") "ERA6AEB103V")
        (field (name "TOLERANCE") "0.1%")
        (field (name "COPYRIGHT") "Copyright C 2015 Accelerated Designs. All rights reserved")
      )
      (libsource (lib "eagle-import") (part "Controller Board_178037_ERA-6AEB103V"))
    )
    (comp (ref "R24")
      (value "10k")
      (footprint "eagle-import:RC0805N")
      (fields
        (field (name "DIGIKEYPARTNUMBER") "P10KDATRND")
        (field (name "MANUFACTURER_PART_NUMBER") "ERA6AEB103V")
        (field (name "TOLERANCE") "0.1%")
        (field (name "COPYRIGHT") "Copyright C 2015 Accelerated Designs. All rights reserved")
      )
      (libsource (lib "eagle-import") (part "Controller Board_178037_ERA-6AEB103V"))
    )
    (comp (ref "R25")
      (value "10k")
      (footprint "eagle-import:RC0805N")
      (fields
        (field (name "DIGIKEYPARTNUMBER") "P10KDATRND")
        (field (name "MANUFACTURER_PART_NUMBER") "ERA6AEB103V")
        (field (name "TOLERANCE") "0.1%")
        (field (name "COPYRIGHT") "Copyright C 2015 Accelerated Designs. All rights reserved")
      )
      (libsource (lib "eagle-import") (part "Controller Board_178037_ERA-6AEB103V"))
    )
    (comp (ref "R26")
      (value "10k")
      (footprint "eagle-import:RC0805N")
      (fields
        (field (name "DIGIKEYPARTNUMBER") "P10KDATRND")
        (field (name "MANUFACTURER_PART_NUMBER") "ERA6AEB103V")
        (field (name "TOLERANCE") "0.1%")
        (field (name "COPYRIGHT") "Copyright C 2015 Accelerated Designs. All rights reserved")
      )
      (libsource (lib "eagle-import") (part "Controller Board_178037_ERA-6AEB103V"))
    )
    (comp (ref "R27")
      (value "10k")
      (footprint "eagle-import:RC0805N")
      (fields
        (field (name "DIGIKEYPARTNUMBER") "P10KDATRND")
        (field (name "MANUFACTURER_PART_NUMBER") "ERA6AEB103V")
        (field (name "TOLERANCE") "0.1%")
        (field (name "COPYRIGHT") "Copyright C 2015 Accelerated Designs. All rights reserved")
      )
      (libsource (lib "eagle-import") (part "Controller Board_178037_ERA-6AEB103V"))
    )
    (comp (ref "R28")
      (value "10k")
      (footprint "eagle-import:RC0805N")
      (fields
        (field (name "DIGIKEYPARTNUMBER") "P10KDATRND")
        (field (name "MANUFACTURER_PART_NUMBER") "ERA6AEB103V")
        (field (name "TOLERANCE") "0.1%")
        (field (name "COPYRIGHT") "Copyright C 2015 Accelerated Designs. All rights reserved")
      )
      (libsource (lib "eagle-import") (part "Controller Board_178037_ERA-6AEB103V"))
    )
    (comp (ref "R29")
      (value "10k")
      (footprint "eagle-import:RC0805N")
      (fields
        (field (name "DIGIKEYPARTNUMBER") "P10KDATRND")
        (field (name "MANUFACTURER_PART_NUMBER") "ERA6AEB103V")
        (field (name "TOLERANCE") "0.1%")
        (field (name "COPYRIGHT") "Copyright C 2015 Accelerated Designs. All rights reserved")
      )
      (libsource (lib "eagle-import") (part "Controller Board_178037_ERA-6AEB103V"))
    )
    (comp (ref "R30")
      (value "20R")
      (footprint "eagle-import:RC0603N-M")
      (fields (field (name "MANUFACTURER_PART_NUMBER") "RC0603JR0720RL"))
      (libsource (lib "eagle-import") (part "RC0603JR-0720RLRC0603N-M"))
    )
    (comp (ref "R31")
      (value "20R")
      (footprint "eagle-import:RC0603N-M")
      (fields (field (name "MANUFACTURER_PART_NUMBER") "RC0603JR0720RL"))
      (libsource (lib "eagle-import") (part "RC0603JR-0720RLRC0603N-M"))
    )
    (comp (ref "R32")
      (value "20R")
      (footprint "eagle-import:RC0603N-M")
      (fields (field (name "MANUFACTURER_PART_NUMBER") "RC0603JR0720RL"))
      (libsource (lib "eagle-import") (part "RC0603JR-0720RLRC0603N-M"))
    )
    (comp (ref "R33")
      (value "340R")
      (footprint "eagle-import:RC0603N")
      (fields
        (field (name "DIGIKEYPARTNUMBER") "311340HRTRND")
        (field (name "MANUFACTURER_PART_NUMBER") "RC0603FR07340RL")
        (field (name "NEWARKPARTNUMBER") "66R2325")
        (field (name "COPYRIGHT") "Copyright C 2015 Accelerated Designs. All rights reserved")
      )
      (libsource (lib "eagle-import") (part "RC0603FR-07340RL"))
    )
    (comp (ref "R38")
      (value "NF")
      (footprint "eagle-import:RC0805N")
      (fields
        (field (name "DIGIKEYPARTNUMBER") "P10KDATRND")
        (field (name "MANUFACTURER_PART_NUMBER") "ERA6AEB103V")
        (field (name "TOLERANCE") "0.1%")
        (field (name "COPYRIGHT") "Copyright C 2015 Accelerated Designs. All rights reserved")
      )
      (libsource (lib "eagle-import") (part "Controller Board_178037_ERA-6AEB103V"))
    )
    (comp (ref "R39")
      (value "100k")
      (footprint "eagle-import:RC0603N-M")
      (fields (field (name "MANUFACTURER_PART_NUMBER") "RC0603JR07100KL"))
      (libsource (lib "eagle-import") (part "RC0603JR-07100KLRC0603N-M"))
    )
    (comp (ref "R40")
      (value "100k")
      (footprint "eagle-import:RC0603N-M")
      (fields (field (name "MANUFACTURER_PART_NUMBER") "RC0603JR07100KL"))
      (libsource (lib "eagle-import") (part "RC0603JR-07100KLRC0603N-M"))
    )
    (comp (ref "R41")
      (value "10k")
      (footprint "eagle-import:RC0805N")
      (fields
        (field (name "DIGIKEYPARTNUMBER") "P10KDATRND")
        (field (name "MANUFACTURER_PART_NUMBER") "ERA6AEB103V")
        (field (name "TOLERANCE") "0.1%")
        (field (name "COPYRIGHT") "Copyright C 2015 Accelerated Designs. All rights reserved")
      )
      (libsource (lib "eagle-import") (part "Controller Board_178037_ERA-6AEB103V"))
    )
    (comp (ref "R42")
      (value "100k")
      (footprint "eagle-import:RC0603N-M")
      (fields (field (name "MANUFACTURER_PART_NUMBER") "RC0603JR07100KL"))
      (libsource (lib "eagle-import") (part "RC0603JR-07100KLRC0603N-M"))
    )
    (comp (ref "R43")
      (value "10k")
      (footprint "eagle-import:RC0805N")
      (fields
        (field (name "DIGIKEYPARTNUMBER") "P10KDATRND")
        (field (name "MANUFACTURER_PART_NUMBER") "ERA6AEB103V")
        (field (name "TOLERANCE") "0.1%")
        (field (name "COPYRIGHT") "Copyright C 2015 Accelerated Designs. All rights reserved")
      )
      (libsource (lib "eagle-import") (part "Controller Board_178037_ERA-6AEB103V"))
    )
    (comp (ref "R45")
      (value "10k")
      (footprint "eagle-import:RC0805N")
      (fields
        (field (name "DIGIKEYPARTNUMBER") "P10KDATRND")
        (field (name "MANUFACTURER_PART_NUMBER") "ERA6AEB103V")
        (field (name "TOLERANCE") "0.1%")
        (field (name "COPYRIGHT") "Copyright C 2015 Accelerated Designs. All rights reserved")
      )
      (libsource (lib "eagle-import") (part "Controller Board_178037_ERA-6AEB103V"))
    )
    (comp (ref "R50")
      (value "12k")
      (footprint "eagle-import:RC0402N-M")
      (fields (field (name "MANUFACTURER_PART_NUMBER") "RC0402FR0712KL"))
      (libsource (lib "eagle-import") (part "RC0402FR-0712KLRC0402N-M"))
    )
    (comp (ref "R51")
      (value "10k")
      (footprint "eagle-import:RC0805N")
      (fields
        (field (name "DIGIKEYPARTNUMBER") "P10KDATRND")
        (field (name "MANUFACTURER_PART_NUMBER") "ERA6AEB103V")
        (field (name "TOLERANCE") "0.1%")
        (field (name "COPYRIGHT") "Copyright C 2015 Accelerated Designs. All rights reserved")
      )
      (libsource (lib "eagle-import") (part "ERA-6AEB103V"))
    )
    (comp (ref "R52")
      (value "12.4k")
      (footprint "eagle-import:YAG_R0402-M")
      (fields (field (name "MANUFACTURER_PART_NUMBER") "RC0402FR0712K4L"))
      (libsource (lib "eagle-import") (part "RC0402FR-0712K4LYAG_R0402-M"))
    )
    (comp (ref "TP1")
      (value "TPB2,54")
      (footprint "eagle-import:B2,54")
      (libsource (lib "eagle-import") (part "TPB2,54"))
    )
    (comp (ref "TP2")
      (value "TPB2,54")
      (footprint "eagle-import:B2,54")
      (libsource (lib "eagle-import") (part "TPB2,54"))
    )
    (comp (ref "TP3")
      (value "TPB2,54")
      (footprint "eagle-import:B2,54")
      (libsource (lib "eagle-import") (part "TPB2,54"))
    )
    (comp (ref "U$2")
      (value "MICROSD")
      (footprint "eagle-import:MICROSD")
      (libsource (lib "eagle-import") (part "MICROSD"))
    )
    (comp (ref "U1")
      (value "AAT3620_BATT_CHARGER")
      (footprint "eagle-import:AAT3620_TDFN")
      (libsource (lib "eagle-import") (part "AAT3620_BATT_CHARGER"))
    )
    (comp (ref "U2")
      (value "8 CH")
      (footprint "eagle-import:21-0055H_16-M")
      (fields
        (field (name "DIGIKEYPARTNUMBER") "MAX11608EEE+ND")
        (field (name "MANUFACTURER_PART_NUMBER") "MAX11608EEE+")
        (field (name "COPYRIGHT") "Copyright C 2015 Accelerated Designs. All rights reserved")
      )
      (libsource (lib "eagle-import") (part "MAX11608EEE+21-0055H_16-M"))
    )
    (comp (ref "U5")
      (value "LAN9512-JZXQFN64_9X9MC-M")
      (footprint "eagle-import:QFN64_9X9MC-M")
      (fields (field (name "MANUFACTURER_PART_NUMBER") "LAN9512JZX"))
      (libsource (lib "eagle-import") (part "LAN9512-JZXQFN64_9X9MC-M"))
    )
    (comp (ref "U6")
      (value "COMPUTE_MODULE")
      (footprint "eagle-import:SO-DIMM")
      (libsource (lib "eagle-import") (part "COMPUTE_MODULE"))
    )
    (comp (ref "U7")
      (value "ESD5384")
      (footprint "eagle-import:WLCSP9")
      (libsource (lib "eagle-import") (part "ESD5384"))
    )
    (comp (ref "U8")
      (value "PEC12R")
      (footprint "eagle-import:PEC12R")
      (libsource (lib "eagle-import") (part "PEC12R"))
    )
    (comp (ref "U9")
      (value "PEC12R")
      (footprint "eagle-import:PEC12R")
      (libsource (lib "eagle-import") (part "PEC12R"))
    )
    (comp (ref "U12")
      (value "APPLE_2.0C_COPROCESSOR")
      (footprint "eagle-import:PG-USON-8-1")
      (libsource (lib "eagle-import") (part "APPLE_2.0C_COPROCESSOR"))
    )
    (comp (ref "U17")
      (value "ATTINY10-TSHR6ST1-M")
      (footprint "eagle-import:6ST1-M")
      (fields (field (name "MANUFACTURER_PART_NUMBER") "ATTINY10TSHR"))
      (libsource (lib "eagle-import") (part "ATTINY10-TSHR6ST1-M"))
    )
    (comp (ref "U18")
      (value "ESP12ESMD")
      (footprint "eagle-import:ESP12E-SMD")
      (libsource (lib "eagle-import") (part "ESP12ESMD"))
    )
    (comp (ref "U19")
      (value "WM8960")
      (footprint "eagle-import:32QFN")
      (libsource (lib "eagle-import") (part "WM8960"))
    )
    (comp (ref "Y1")
      (value "DSC6001")
      (footprint "eagle-import:4-VFLGA")
      (libsource (lib "eagle-import") (part "DSC6001"))
    )
  )
  (nets
    (net (code "1") (name "+1V8") (class "Default")
      (node (ref "C17") (pin "2") (pinfunction "2_2") (pintype "passive"))
      (node (ref "C18") (pin "2") (pinfunction "2_2") (pintype "passive"))
      (node (ref "L3") (pin "P$2") (pinfunction "2_P$2") (pintype "passive"))
      (node (ref "R39") (pin "1") (pinfunction "11_1") (pintype "passive"))
      (node (ref "U16") (pin "4") (pinfunction "SNS_4") (pintype "bidirectional"))
      (node (ref "U6") (pin "183") (pinfunction "1V8_183") (pintype "bidirectional"))
      (node (ref "U6") (pin "184") (pinfunction "1V8_184") (pintype "bidirectional"))
      (node (ref "U6") (pin "185") (pinfunction "1V8_185") (pintype "bidirectional"))
      (node (ref "U6") (pin "186") (pinfunction "1V8_186") (pintype "bidirectional"))
    )
    (net (code "2") (name "+3V3") (class "Default")
      (node (ref "C16") (pin "2") (pinfunction "2_2") (pintype "passive"))
      (node (ref "C20") (pin "2") (pinfunction "2_2") (pintype "passive"))
      (node (ref "C21") (pin "2") (pinfunction "2_2") (pintype "passive"))
      (node (ref "C22") (pin "2") (pinfunction "2_2") (pintype "passive"))
      (node (ref "C23") (pin "2") (pinfunction "2_2") (pintype "passive"))
      (node (ref "C35") (pin "2") (pinfunction "2_2") (pintype "passive"))
      (node (ref "C36") (pin "2") (pinfunction "2_2") (pintype "passive"))
      (node (ref "C41") (pin "2") (pinfunction "2_2") (pintype "passive"))
      (node (ref "C60") (pin "2") (pinfunction "2_2") (pintype "passive"))
      (node (ref "C61") (pin "2") (pinfunction "2_2") (pintype "passive"))
      (node (ref "C62") (pin "2") (pinfunction "2_2") (pintype "passive"))
      (node (ref "C63") (pin "2") (pinfunction "2_2") (pintype "passive"))
      (node (ref "C64") (pin "2") (pinfunction "2_2") (pintype "passive"))
      (node (ref "C68") (pin "2") (pinfunction "2_2") (pintype "passive"))
      (node (ref "C9") (pin "2") (pinfunction "2_2") (pintype "passive"))
      (node (ref "D2") (pin "A") (pinfunction "A_A") (pintype "passive"))
      (node (ref "D3") (pin "A") (pinfunction "A_A") (pintype "passive"))
      (node (ref "FB2") (pin "2") (pinfunction "2_2") (pintype "passive"))
      (node (ref "J1") (pin "3") (pinfunction "3_3") (pintype "bidirectional"))
      (node (ref "J10") (pin "2") (pinfunction "2_2") (pintype "bidirectional"))
      (node (ref "J11") (pin "2") (pinfunction "2_2") (pintype "bidirectional"))
      (node (ref "J4") (pin "1") (pinfunction "1_1") (pintype "bidirectional"))
      (node (ref "J5") (pin "11") (pinfunction "11_11") (pintype "bidirectional"))
      (node (ref "J8") (pin "2") (pinfunction "2_2") (pintype "bidirectional"))
      (node (ref "L2") (pin "P$2") (pinfunction "2_P$2") (pintype "passive"))
      (node (ref "R23") (pin "1") (pinfunction "11_1") (pintype "passive"))
      (node (ref "R25") (pin "1") (pinfunction "11_1") (pintype "passive"))
      (node (ref "R26") (pin "1") (pinfunction "11_1") (pintype "passive"))
      (node (ref "R29") (pin "1") (pinfunction "11_1") (pintype "passive"))
      (node (ref "R32") (pin "2") (pinfunction "22_2") (pintype "passive"))
      (node (ref "R38") (pin "1") (pinfunction "11_1") (pintype "passive"))
      (node (ref "R51") (pin "2") (pinfunction "22_2") (pintype "passive"))
      (node (ref "R6") (pin "1") (pinfunction "11_1") (pintype "passive"))
      (node (ref "R7") (pin "1") (pinfunction "11_1") (pintype "passive"))
      (node (ref "U$2") (pin "4") (pinfunction "VDD_4") (pintype "bidirectional"))
      (node (ref "U10") (pin "16") (pinfunction "VOS_16") (pintype "bidirectional"))
      (node (ref "U12") (pin "7") (pinfunction "RST_7") (pintype "bidirectional"))
      (node (ref "U12") (pin "8") (pinfunction "VCC_8") (pintype "bidirectional"))
      (node (ref "U17") (pin "5") (pinfunction "VCC_5") (pintype "power_in"))
      (node (ref "U18") (pin "VCC") (pinfunction "VCC_VCC") (pintype "bidirectional"))
      (node (ref "U19") (pin "10") (pinfunction "DBVDD_10") (pintype "bidirectional"))
      (node (ref "U19") (pin "21") (pinfunction "SPKVDD_21") (pintype "bidirectional"))
      (node (ref "U19") (pin "26") (pinfunction "SPKVDD_26") (pintype "bidirectional"))
      (node (ref "U19") (pin "8") (pinfunction "DCVDD_8") (pintype "bidirectional"))
      (node (ref "U2") (pin "16") (pinfunction "VDD_16") (pintype "power_in"))
      (node (ref "U5") (pin "11") (pinfunction "VBUS_DET_11") (pintype "power_in"))
      (node (ref "U5") (pin "19") (pinfunction "VDD33IO_2_19") (pintype "power_in"))
      (node (ref "U5") (pin "27") (pinfunction "VDD33IO_3_27") (pintype "power_in"))
      (node (ref "U5") (pin "33") (pinfunction "VDD33IO_4_33") (pintype "power_in"))
      (node (ref "U5") (pin "39") (pinfunction "VDD33IO_5_39") (pintype "power_in"))
      (node (ref "U5") (pin "40") (pinfunction "TEST3_40") (pintype "passive"))
      (node (ref "U5") (pin "46") (pinfunction "VDD33IO_46") (pintype "power_in"))
      (node (ref "U6") (pin "189") (pinfunction "VDAC_189") (pintype "bidirectional"))
      (node (ref "U6") (pin "190") (pinfunction "VDAC_190") (pintype "bidirectional"))
      (node (ref "U6") (pin "191") (pinfunction "3V3_191") (pintype "bidirectional"))
      (node (ref "U6") (pin "192") (pinfunction "3V3_192") (pintype "bidirectional"))
      (node (ref "U6") (pin "193") (pinfunction "3V3_193") (pintype "bidirectional"))
      (node (ref "U6") (pin "194") (pinfunction "3V3_194") (pintype "bidirectional"))
      (node (ref "U6") (pin "197") (pinfunction "VBAT_197") (pintype "bidirectional"))
      (node (ref "U6") (pin "198") (pinfunction "VBAT_198") (pintype "bidirectional"))
      (node (ref "U6") (pin "199") (pinfunction "VBAT_199") (pintype "bidirectional"))
      (node (ref "U6") (pin "200") (pinfunction "VBAT_200") (pintype "bidirectional"))
      (node (ref "U6") (pin "39") (pinfunction "GPIO0-27_VDD_39") (pintype "bidirectional"))
      (node (ref "U6") (pin "4") (pinfunction "SDX_VDD_4") (pintype "bidirectional"))
      (node (ref "U6") (pin "40") (pinfunction "GPIO0-27_VDD_40") (pintype "bidirectional"))
      (node (ref "U6") (pin "41") (pinfunction "GPIO28-45_VDD_41") (pintype "bidirectional"))
      (node (ref "U6") (pin "42") (pinfunction "GPIO28-45_VDD_42") (pintype "bidirectional"))
      (node (ref "U6") (pin "6") (pinfunction "SDX_VDD_6") (pintype "bidirectional"))
      (node (ref "Y1") (pin "1") (pinfunction "EN_1") (pintype "bidirectional"))
      (node (ref "Y1") (pin "4") (pinfunction "VDD_4") (pintype "bidirectional"))
    )
    (net (code "3") (name "+5V") (class "Default")
      (node (ref "C33") (pin "2") (pinfunction "2_2") (pintype "passive"))
      (node (ref "J2") (pin "1") (pinfunction "5V_1") (pintype "bidirectional"))
      (node (ref "J2") (pin "2") (pinfunction "5V_2") (pintype "bidirectional"))
      (node (ref "J9") (pin "1") (pinfunction "VCC_1") (pintype "bidirectional"))
      (node (ref "Q6") (pin "G") (pinfunction "G_G") (pintype "passive"))
      (node (ref "U3") (pin "A1") (pinfunction "VOUT_A1") (pintype "output"))
      (node (ref "U3") (pin "A2") (pinfunction "VOUT_A2") (pintype "output"))
      (node (ref "U7") (pin "A1") (pinfunction "5V_A1") (pintype "bidirectional"))
      (node (ref "U7") (pin "B1") (pinfunction "RPU2_B1") (pintype "bidirectional"))
      (node (ref "U7") (pin "C1") (pinfunction "RPU_C1") (pintype "bidirectional"))
    )
    (net (code "4") (name "3.3V_A") (class "Default")
      (node (ref "C19") (pin "2") (pinfunction "2_2") (pintype "passive"))
      (node (ref "C24") (pin "2") (pinfunction "2_2") (pintype "passive"))
      (node (ref "C29") (pin "1") (pinfunction "1_1") (pintype "passive"))
      (node (ref "C37") (pin "1") (pinfunction "1_1") (pintype "passive"))
      (node (ref "C55") (pin "2") (pinfunction "2_2") (pintype "passive"))
      (node (ref "C57") (pin "2") (pinfunction "2_2") (pintype "passive"))
      (node (ref "C58") (pin "2") (pinfunction "2_2") (pintype "passive"))
      (node (ref "C59") (pin "2") (pinfunction "2_2") (pintype "passive"))
      (node (ref "FB2") (pin "1") (pinfunction "1_1") (pintype "passive"))
      (node (ref "J10") (pin "1") (pinfunction "1_1") (pintype "bidirectional"))
      (node (ref "MIC1") (pin "6") (pinfunction "VDD_6") (pintype "bidirectional"))
      (node (ref "MIC2") (pin "6") (pinfunction "VDD_6") (pintype "bidirectional"))
      (node (ref "U19") (pin "32") (pinfunction "AVDD_32") (pintype "bidirectional"))
      (node (ref "U5") (pin "10") (pinfunction "VDD33A_3_10") (pintype "power_in"))
      (node (ref "U5") (pin "49") (pinfunction "VDD33A_4_49") (pintype "power_in"))
      (node (ref "U5") (pin "5") (pinfunction "VDD33A_2_5") (pintype "power_in"))
      (node (ref "U5") (pin "51") (pinfunction "VDD33A_5_51") (pintype "power_in"))
      (node (ref "U5") (pin "54") (pinfunction "VDD33A_6_54") (pintype "power_in"))
      (node (ref "U5") (pin "57") (pinfunction "VDD33A_7_57") (pintype "power_in"))
      (node (ref "U5") (pin "64") (pinfunction "VDD33A_64") (pintype "power_in"))
    )
    (net (code "5") (name "BATT_CNTL") (class "Default")
      (node (ref "Q2") (pin "G") (pinfunction "G_G") (pintype "passive"))
      (node (ref "R10") (pin "1") (pinfunction "11_1") (pintype "passive"))
      (node (ref "TP3") (pin "TP") (pinfunction "TP_TP") (pintype "input"))
      (node (ref "U17") (pin "3") (pinfunction "(PCINT1/TPICLK)_PB1_3") (pintype "bidirectional"))
    )
    (net (code "6") (name "BATT_OUTPUT") (class "Default")
      (node (ref "C11") (pin "2") (pinfunction "2_2") (pintype "passive"))
      (node (ref "C34") (pin "2") (pinfunction "2_2") (pintype "passive"))
      (node (ref "C8") (pin "2") (pinfunction "2_2") (pintype "passive"))
      (node (ref "D6") (pin "C") (pinfunction "12_C") (pintype "passive"))
      (node (ref "L1") (pin "P$2") (pinfunction "2_P$2") (pintype "passive"))
      (node (ref "Q1") (pin "D") (pinfunction "D_D") (pintype "passive"))
      (node (ref "R4") (pin "1") (pinfunction "11_1") (pintype "passive"))
      (node (ref "R48") (pin "1") (pinfunction "11_1") (pintype "passive"))
      (node (ref "R49") (pin "1") (pinfunction "11_1") (pintype "passive"))
      (node (ref "U10") (pin "10") (pinfunction "AVIN_10") (pintype "bidirectional"))
      (node (ref "U10") (pin "11") (pinfunction "PVIN_11") (pintype "bidirectional"))
      (node (ref "U10") (pin "12") (pinfunction "PVIN_12") (pintype "bidirectional"))
      (node (ref "U11") (pin "1") (pinfunction "VCC_1") (pintype "power_in"))
      (node (ref "U16") (pin "7") (pinfunction "VIN_7") (pintype "bidirectional"))
      (node (ref "U3") (pin "A3") (pinfunction "VIN_A3") (pintype "input"))
      (node (ref "U3") (pin "B3") (pinfunction "EN_B3") (pintype "input"))
    )
    (net (code "7") (name "EMMC_DISABLE_N") (class "Default")
      (node (ref "U6") (pin "2") (pinfunction "EMMC_DISABLE_N_2") (pintype "bidirectional"))
    )
    (net (code "8") (name "EMMC_EN_N_1V8") (class "Default")
      (node (ref "U6") (pin "90") (pinfunction "EMMC_EN_N_1V8_90") (pintype "bidirectional"))
    )
    (net (code "9") (name "ENCODER1_A") (class "Default")
      (node (ref "C13") (pin "2") (pinfunction "2_2") (pintype "bidirectional"))
      (node (ref "R42") (pin "1") (pinfunction "11_1") (pintype "passive"))
      (node (ref "R5") (pin "2") (pinfunction "22_2") (pintype "passive"))
      (node (ref "U6") (pin "28") (pinfunction "GPIO28_28") (pintype "bidirectional"))
    )
    (net (code "10") (name "ENCODER1_B") (class "Default")
      (node (ref "C12") (pin "2") (pinfunction "2_2") (pintype "bidirectional"))
      (node (ref "R24") (pin "2") (pinfunction "22_2") (pintype "passive"))
      (node (ref "U6") (pin "5") (pinfunction "GPIO1_5") (pintype "bidirectional"))
    )
    (net (code "11") (name "ENCODER2_A") (class "Default")
      (node (ref "C15") (pin "2") (pinfunction "2_2") (pintype "bidirectional"))
      (node (ref "R27") (pin "2") (pinfunction "22_2") (pintype "passive"))
      (node (ref "U6") (pin "76") (pinfunction "GPIO42_76") (pintype "bidirectional"))
    )
    (net (code "12") (name "ENCODER2_B") (class "Default")
      (node (ref "C14") (pin "2") (pinfunction "2_2") (pintype "bidirectional"))
      (node (ref "R28") (pin "2") (pinfunction "22_2") (pintype "passive"))
      (node (ref "U6") (pin "78") (pinfunction "GPIO43_78") (pintype "bidirectional"))
    )
    (net (code "13") (name "GND") (class "Default")
      (node (ref "C1") (pin "1") (pinfunction "1_1") (pintype "passive"))
      (node (ref "C10") (pin "2") (pinfunction "2_2") (pintype "passive"))
      (node (ref "C11") (pin "1") (pinfunction "1_1") (pintype "passive"))
      (node (ref "C12") (pin "1") (pinfunction "1_1") (pintype "bidirectional"))
      (node (ref "C13") (pin "1") (pinfunction "1_1") (pintype "bidirectional"))
      (node (ref "C14") (pin "1") (pinfunction "1_1") (pintype "bidirectional"))
      (node (ref "C15") (pin "1") (pinfunction "1_1") (pintype "bidirectional"))
      (node (ref "C16") (pin "1") (pinfunction "1_1") (pintype "passive"))
      (node (ref "C17") (pin "1") (pinfunction "1_1") (pintype "passive"))
      (node (ref "C19") (pin "1") (pinfunction "1_1") (pintype "passive"))
      (node (ref "C2") (pin "1") (pinfunction "1_1") (pintype "passive"))
      (node (ref "C20") (pin "1") (pinfunction "1_1") (pintype "passive"))
      (node (ref "C21") (pin "1") (pinfunction "1_1") (pintype "passive"))
      (node (ref "C22") (pin "1") (pinfunction "1_1") (pintype "passive"))
      (node (ref "C23") (pin "1") (pinfunction "1_1") (pintype "passive"))
      (node (ref "C24") (pin "1") (pinfunction "1_1") (pintype "passive"))
      (node (ref "C25") (pin "2") (pinfunction "2_2") (pintype "passive"))
      (node (ref "C26") (pin "2") (pinfunction "2_2") (pintype "passive"))
      (node (ref "C27") (pin "1") (pinfunction "11_1") (pintype "passive"))
      (node (ref "C28") (pin "1") (pinfunction "11_1") (pintype "passive"))
      (node (ref "C29") (pin "2") (pinfunction "2_2") (pintype "passive"))
      (node (ref "C3") (pin "1") (pinfunction "1_1") (pintype "passive"))
      (node (ref "C31") (pin "1") (pinfunction "11_1") (pintype "passive"))
      (node (ref "C32") (pin "1") (pinfunction "11_1") (pintype "passive"))
      (node (ref "C33") (pin "1") (pinfunction "1_1") (pintype "passive"))
      (node (ref "C34") (pin "1") (pinfunction "1_1") (pintype "passive"))
      (node (ref "C35") (pin "1") (pinfunction "1_1") (pintype "passive"))
      (node (ref "C36") (pin "1") (pinfunction "1_1") (pintype "passive"))
      (node (ref "C37") (pin "2") (pinfunction "2_2") (pintype "passive"))
      (node (ref "C39") (pin "1") (pinfunction "11_1") (pintype "passive"))
      (node (ref "C4") (pin "1") (pinfunction "1_1") (pintype "passive"))
      (node (ref "C40") (pin "1") (pinfunction "11_1") (pintype "passive"))
      (node (ref "C41") (pin "1") (pinfunction "1_1") (pintype "passive"))
      (node (ref "C5") (pin "1") (pinfunction "1_1") (pintype "passive"))
      (node (ref "C53") (pin "1") (pinfunction "11_1") (pintype "passive"))
      (node (ref "C54") (pin "1") (pinfunction "1_1") (pintype "passive"))
      (node (ref "C55") (pin "1") (pinfunction "1_1") (pintype "passive"))
      (node (ref "C57") (pin "1") (pinfunction "1_1") (pintype "passive"))
      (node (ref "C58") (pin "1") (pinfunction "1_1") (pintype "passive"))
      (node (ref "C59") (pin "1") (pinfunction "1_1") (pintype "passive"))
      (node (ref "C60") (pin "1") (pinfunction "1_1") (pintype "passive"))
      (node (ref "C61") (pin "1") (pinfunction "1_1") (pintype "passive"))
      (node (ref "C62") (pin "1") (pinfunction "1_1") (pintype "passive"))
      (node (ref "C63") (pin "1") (pinfunction "1_1") (pintype "passive"))
      (node (ref "C64") (pin "1") (pinfunction "1_1") (pintype "passive"))
      (node (ref "C65") (pin "1") (pinfunction "1_1") (pintype "passive"))
      (node (ref "C66") (pin "1") (pinfunction "1_1") (pintype "passive"))
      (node (ref "C67") (pin "1") (pinfunction "1_1") (pintype "passive"))
      (node (ref "C68") (pin "1") (pinfunction "1_1") (pintype "passive"))
      (node (ref "C7") (pin "1") (pinfunction "1_1") (pintype "bidirectional"))
      (node (ref "C8") (pin "1") (pinfunction "1_1") (pintype "passive"))
      (node (ref "C9") (pin "1") (pinfunction "1_1") (pintype "passive"))
      (node (ref "D1") (pin "C") (pinfunction "C_C") (pintype "passive"))
      (node (ref "D4") (pin "C") (pinfunction "C_C") (pintype "passive"))
      (node (ref "J1") (pin "4") (pinfunction "4_4") (pintype "bidirectional"))
      (node (ref "J10") (pin "11") (pinfunction "11_11") (pintype "bidirectional"))
      (node (ref "J10") (pin "14") (pinfunction "14_14") (pintype "bidirectional"))
      (node (ref "J10") (pin "17") (pinfunction "17_17") (pintype "bidirectional"))
      (node (ref "J11") (pin "1") (pinfunction "1_1") (pintype "bidirectional"))
      (node (ref "J2") (pin "3") (pinfunction "GND_3") (pintype "bidirectional"))
      (node (ref "J2") (pin "7") (pinfunction "GND_7") (pintype "bidirectional"))
      (node (ref "J3") (pin "4") (pinfunction "ID_4") (pintype "bidirectional"))
      (node (ref "J3") (pin "5") (pinfunction "GND_5") (pintype "power_in"))
      (node (ref "J3") (pin "6") (pinfunction "GND_6") (pintype "power_in"))
      (node (ref "J3") (pin "7") (pinfunction "GND_7") (pintype "power_in"))
      (node (ref "J3") (pin "P$1") (pinfunction "GND_P$1") (pintype "power_in"))
      (node (ref "J3") (pin "P$2") (pinfunction "GND_P$2") (pintype "power_in"))
      (node (ref "J3") (pin "P$3") (pinfunction "GND_P$3") (pintype "power_in"))
      (node (ref "J3") (pin "P$4") (pinfunction "GND_P$4") (pintype "power_in"))
      (node (ref "J4") (pin "4") (pinfunction "4_4") (pintype "bidirectional"))
      (node (ref "J5") (pin "15") (pinfunction "15_15") (pintype "bidirectional"))
      (node (ref "J6") (pin "2") (pinfunction "GND_2") (pintype "power_in"))
      (node (ref "J7") (pin "11") (pinfunction "GND_11") (pintype "bidirectional"))
      (node (ref "J7") (pin "17") (pinfunction "GND_17") (pintype "bidirectional"))
      (node (ref "J7") (pin "2") (pinfunction "GND_2") (pintype "bidirectional"))
      (node (ref "J7") (pin "5") (pinfunction "GND_5") (pintype "bidirectional"))
      (node (ref "J7") (pin "8") (pinfunction "GND_8") (pintype "bidirectional"))
      (node (ref "J7") (pin "P$1") (pinfunction "GND_P$1") (pintype "bidirectional"))
      (node (ref "J7") (pin "P$2") (pinfunction "GND_P$2") (pintype "bidirectional"))
      (node (ref "J7") (pin "P$3") (pinfunction "GND_P$3") (pintype "bidirectional"))
      (node (ref "J7") (pin "P$4") (pinfunction "GND_P$4") (pintype "bidirectional"))
      (node (ref "J9") (pin "4") (pinfunction "GND_4") (pintype "bidirectional"))
      (node (ref "J9") (pin "5") (pinfunction "GND_5") (pintype "bidirectional"))
      (node (ref "J9") (pin "6") (pinfunction "GND_6") (pintype "bidirectional"))
      (node (ref "MIC1") (pin "1") (pinfunction "GND_1") (pintype "bidirectional"))
      (node (ref "MIC1") (pin "2") (pinfunction "GND_2") (pintype "bidirectional"))
      (node (ref "MIC1") (pin "3") (pinfunction "GND_3") (pintype "bidirectional"))
      (node (ref "MIC1") (pin "5") (pinfunction "GND_5") (pintype "bidirectional"))
      (node (ref "MIC2") (pin "1") (pinfunction "GND_1") (pintype "bidirectional"))
      (node (ref "MIC2") (pin "2") (pinfunction "GND_2") (pintype "bidirectional"))
      (node (ref "MIC2") (pin "3") (pinfunction "GND_3") (pintype "bidirectional"))
      (node (ref "MIC2") (pin "5") (pinfunction "GND_5") (pintype "bidirectional"))
      (node (ref "Q2") (pin "S") (pinfunction "S_S") (pintype "passive"))
      (node (ref "Q5") (pin "S") (pinfunction "S_S") (pintype "passive"))
      (node (ref "R10") (pin "2") (pinfunction "22_2") (pintype "passive"))
      (node (ref "R16") (pin "2") (pinfunction "22_2") (pintype "passive"))
      (node (ref "R19") (pin "1") (pinfunction "11_1") (pintype "passive"))
      (node (ref "R20") (pin "1") (pinfunction "11_1") (pintype "passive"))
      (node (ref "R3") (pin "1") (pinfunction "11_1") (pintype "passive"))
      (node (ref "R40") (pin "2") (pinfunction "22_2") (pintype "passive"))
      (node (ref "R41") (pin "2") (pinfunction "22_2") (pintype "passive"))
      (node (ref "R42") (pin "2") (pinfunction "22_2") (pintype "passive"))
      (node (ref "R43") (pin "2") (pinfunction "22_2") (pintype "passive"))
      (node (ref "R45") (pin "2") (pinfunction "22_2") (pintype "passive"))
      (node (ref "R50") (pin "2") (pinfunction "22_2") (pintype "passive"))
      (node (ref "R52") (pin "1") (pinfunction "11_1") (pintype "passive"))
      (node (ref "U$2") (pin "10") (pinfunction "VSS_10") (pintype "bidirectional"))
      (node (ref "U$2") (pin "11") (pinfunction "VSS_11") (pintype "bidirectional"))
      (node (ref "U$2") (pin "12") (pinfunction "VSS_12") (pintype "bidirectional"))
      (node (ref "U$2") (pin "13") (pinfunction "VSS_13") (pintype "bidirectional"))
      (node (ref "U$2") (pin "6") (pinfunction "VSS_6") (pintype "bidirectional"))
      (node (ref "U$2") (pin "9") (pinfunction "VSS_9") (pintype "bidirectional"))
      (node (ref "U1") (pin "2") (pinfunction "PGND_2") (pintype "power_in"))
      (node (ref "U1") (pin "3") (pinfunction "GND_3") (pintype "power_in"))
      (node (ref "U1") (pin "EP") (pinfunction "EP_EP") (pintype "power_in"))
      (node (ref "U10") (pin "14") (pinfunction "PGND_14") (pintype "bidirectional"))
      (node (ref "U10") (pin "15") (pinfunction "PGND_15") (pintype "bidirectional"))
      (node (ref "U10") (pin "17") (pinfunction "PGND_17") (pintype "bidirectional"))
      (node (ref "U10") (pin "3") (pinfunction "FREQ_3") (pintype "bidirectional"))
      (node (ref "U10") (pin "5") (pinfunction "FB_5") (pintype "bidirectional"))
      (node (ref "U10") (pin "6") (pinfunction "AGND_6") (pintype "bidirectional"))
      (node (ref "U11") (pin "2") (pinfunction "GND_2") (pintype "power_in"))
      (node (ref "U12") (pin "1") (pinfunction "GND_1") (pintype "bidirectional"))
      (node (ref "U12") (pin "9") (pinfunction "GND_9") (pintype "bidirectional"))
      (node (ref "U16") (pin "6") (pinfunction "AGND_6") (pintype "bidirectional"))
      (node (ref "U16") (pin "8") (pinfunction "PGND_8") (pintype "bidirectional"))
      (node (ref "U16") (pin "EP") (pinfunction "PGND_EP") (pintype "bidirectional"))
      (node (ref "U17") (pin "2") (pinfunction "GND_2") (pintype "power_in"))
      (node (ref "U18") (pin "GND") (pinfunction "GND_GND") (pintype "bidirectional"))
      (node (ref "U19") (pin "20") (pinfunction "SPKGND_20") (pintype "bidirectional"))
      (node (ref "U19") (pin "24") (pinfunction "SPKGND_24") (pintype "bidirectional"))
      (node (ref "U19") (pin "28") (pinfunction "AGND_28") (pintype "bidirectional"))
      (node (ref "U19") (pin "9") (pinfunction "DGND_9") (pintype "bidirectional"))
      (node (ref "U19") (pin "EP") (pinfunction "GNDPADDLE_EP") (pintype "bidirectional"))
      (node (ref "U2") (pin "15") (pinfunction "GND_15") (pintype "power_in"))
      (node (ref "U3") (pin "C1") (pinfunction "GND_C1") (pintype "power_in"))
      (node (ref "U3") (pin "C2") (pinfunction "GND_C2") (pintype "power_in"))
      (node (ref "U5") (pin "34") (pinfunction "TEST2_34") (pintype "passive"))
      (node (ref "U5") (pin "44") (pinfunction "CLK24_EN_44") (pintype "input"))
      (node (ref "U5") (pin "65") (pinfunction "EPAD_65") (pintype "passive"))
      (node (ref "U6") (pin "1") (pinfunction "GND_1") (pintype "bidirectional"))
      (node (ref "U6") (pin "103") (pinfunction "GND_103") (pintype "bidirectional"))
      (node (ref "U6") (pin "104") (pinfunction "GND_104") (pintype "bidirectional"))
      (node (ref "U6") (pin "109") (pinfunction "GND_109") (pintype "bidirectional"))
      (node (ref "U6") (pin "110") (pinfunction "GND_110") (pintype "bidirectional"))
      (node (ref "U6") (pin "115") (pinfunction "GND_115") (pintype "bidirectional"))
      (node (ref "U6") (pin "116") (pinfunction "GND_116") (pintype "bidirectional"))
      (node (ref "U6") (pin "121") (pinfunction "GND_121") (pintype "bidirectional"))
      (node (ref "U6") (pin "122") (pinfunction "GND_122") (pintype "bidirectional"))
      (node (ref "U6") (pin "127") (pinfunction "GND_127") (pintype "bidirectional"))
      (node (ref "U6") (pin "13") (pinfunction "GND_13") (pintype "bidirectional"))
      (node (ref "U6") (pin "133") (pinfunction "GND_133") (pintype "bidirectional"))
      (node (ref "U6") (pin "134") (pinfunction "GND_134") (pintype "bidirectional"))
      (node (ref "U6") (pin "139") (pinfunction "GND_139") (pintype "bidirectional"))
      (node (ref "U6") (pin "14") (pinfunction "GND_14") (pintype "bidirectional"))
      (node (ref "U6") (pin "140") (pinfunction "GND_140") (pintype "bidirectional"))
      (node (ref "U6") (pin "145") (pinfunction "GND_145") (pintype "bidirectional"))
      (node (ref "U6") (pin "146") (pinfunction "GND_146") (pintype "bidirectional"))
      (node (ref "U6") (pin "151") (pinfunction "GND_151") (pintype "bidirectional"))
      (node (ref "U6") (pin "152") (pinfunction "GND_152") (pintype "bidirectional"))
      (node (ref "U6") (pin "157") (pinfunction "GND_157") (pintype "bidirectional"))
      (node (ref "U6") (pin "163") (pinfunction "GND_163") (pintype "bidirectional"))
      (node (ref "U6") (pin "164") (pinfunction "GND_164") (pintype "bidirectional"))
      (node (ref "U6") (pin "169") (pinfunction "GND_169") (pintype "bidirectional"))
      (node (ref "U6") (pin "170") (pinfunction "GND_170") (pintype "bidirectional"))
      (node (ref "U6") (pin "181") (pinfunction "GND_181") (pintype "bidirectional"))
      (node (ref "U6") (pin "182") (pinfunction "GND_182") (pintype "bidirectional"))
      (node (ref "U6") (pin "187") (pinfunction "GND_187") (pintype "bidirectional"))
      (node (ref "U6") (pin "188") (pinfunction "GND_188") (pintype "bidirectional"))
      (node (ref "U6") (pin "19") (pinfunction "GND_19") (pintype "bidirectional"))
      (node (ref "U6") (pin "195") (pinfunction "GND_195") (pintype "bidirectional"))
      (node (ref "U6") (pin "196") (pinfunction "GND_196") (pintype "bidirectional"))
      (node (ref "U6") (pin "20") (pinfunction "GND_20") (pintype "bidirectional"))
      (node (ref "U6") (pin "25") (pinfunction "GND_25") (pintype "bidirectional"))
      (node (ref "U6") (pin "26") (pinfunction "GND_26") (pintype "bidirectional"))
      (node (ref "U6") (pin "31") (pinfunction "GND_31") (pintype "bidirectional"))
      (node (ref "U6") (pin "32") (pinfunction "GND_32") (pintype "bidirectional"))
      (node (ref "U6") (pin "37") (pinfunction "GND_37") (pintype "bidirectional"))
      (node (ref "U6") (pin "38") (pinfunction "GND_38") (pintype "bidirectional"))
      (node (ref "U6") (pin "43") (pinfunction "GND_43") (pintype "bidirectional"))
      (node (ref "U6") (pin "44") (pinfunction "GND_44") (pintype "bidirectional"))
      (node (ref "U6") (pin "49") (pinfunction "GND_49") (pintype "bidirectional"))
      (node (ref "U6") (pin "50") (pinfunction "GND_50") (pintype "bidirectional"))
      (node (ref "U6") (pin "55") (pinfunction "GND_55") (pintype "bidirectional"))
      (node (ref "U6") (pin "56") (pinfunction "GND_56") (pintype "bidirectional"))
      (node (ref "U6") (pin "61") (pinfunction "GND_61") (pintype "bidirectional"))
      (node (ref "U6") (pin "62") (pinfunction "GND_62") (pintype "bidirectional"))
      (node (ref "U6") (pin "67") (pinfunction "GND_67") (pintype "bidirectional"))
      (node (ref "U6") (pin "68") (pinfunction "GND_68") (pintype "bidirectional"))
      (node (ref "U6") (pin "7") (pinfunction "GND_7") (pintype "bidirectional"))
      (node (ref "U6") (pin "73") (pinfunction "GND_73") (pintype "bidirectional"))
      (node (ref "U6") (pin "74") (pinfunction "GND_74") (pintype "bidirectional"))
      (node (ref "U6") (pin "79") (pinfunction "GND_79") (pintype "bidirectional"))
      (node (ref "U6") (pin "8") (pinfunction "GND_8") (pintype "bidirectional"))
      (node (ref "U6") (pin "80") (pinfunction "GND_80") (pintype "bidirectional"))
      (node (ref "U6") (pin "85") (pinfunction "GND_85") (pintype "bidirectional"))
      (node (ref "U6") (pin "86") (pinfunction "GND_86") (pintype "bidirectional"))
      (node (ref "U6") (pin "91") (pinfunction "GND_91") (pintype "bidirectional"))
      (node (ref "U6") (pin "92") (pinfunction "GND_92") (pintype "bidirectional"))
      (node (ref "U6") (pin "97") (pinfunction "GND_97") (pintype "bidirectional"))
      (node (ref "U6") (pin "98") (pinfunction "GND_98") (pintype "bidirectional"))
      (node (ref "U6") (pin "G1") (pinfunction "G1_G1") (pintype "bidirectional"))
      (node (ref "U6") (pin "G2") (pinfunction "G2_G2") (pintype "bidirectional"))
      (node (ref "U7") (pin "B2") (pinfunction "GND_B2") (pintype "bidirectional"))
      (node (ref "U7") (pin "C2") (pinfunction "GND_C2") (pintype "bidirectional"))
      (node (ref "U8") (pin "C") (pinfunction "C_C") (pintype "bidirectional"))
      (node (ref "U9") (pin "C") (pinfunction "C_C") (pintype "bidirectional"))
      (node (ref "Y1") (pin "2") (pinfunction "GND_2") (pintype "bidirectional"))
    )
    (net (code "14") (name "GPCLK1") (class "Default")
      (node (ref "R40") (pin "1") (pinfunction "11_1") (pintype "passive"))
      (node (ref "U5") (pin "61") (pinfunction "XI_61") (pintype "input"))
      (node (ref "U6") (pin "82") (pinfunction "GPIO44_82") (pintype "bidirectional"))
    )
    (net (code "15") (name "GPIO36") (class "Default")
      (node (ref "U6") (pin "58") (pinfunction "GPIO36_58") (pintype "bidirectional"))
    )
    (net (code "16") (name "GPIO37") (class "Default")
      (node (ref "U6") (pin "60") (pinfunction "GPIO37_60") (pintype "bidirectional"))
    )
    (net (code "17") (name "HDMI_CEC") (class "Default")
      (node (ref "Q6") (pin "S") (pinfunction "S_S") (pintype "passive"))
      (node (ref "R38") (pin "2") (pinfunction "22_2") (pintype "passive"))
      (node (ref "U6") (pin "171") (pinfunction "HDMI_CEC_171") (pintype "bidirectional"))
    )
    (net (code "18") (name "HDMI_CK_N") (class "Default")
      (node (ref "J7") (pin "12") (pinfunction "CLK_N_12") (pintype "bidirectional"))
      (node (ref "U6") (pin "111") (pinfunction "HDMI_CK_N_111") (pintype "bidirectional"))
    )
    (net (code "19") (name "HDMI_CK_P") (class "Default")
      (node (ref "J7") (pin "10") (pinfunction "CLK_P_10") (pintype "bidirectional"))
      (node (ref "U6") (pin "113") (pinfunction "HDMI_CK_P_113") (pintype "bidirectional"))
    )
    (net (code "20") (name "HDMI_D0_N") (class "Default")
      (node (ref "J7") (pin "9") (pinfunction "TX0_N_9") (pintype "bidirectional"))
      (node (ref "U6") (pin "117") (pinfunction "HDMI_D0_N_117") (pintype "bidirectional"))
    )
    (net (code "21") (name "HDMI_D0_P") (class "Default")
      (node (ref "J7") (pin "7") (pinfunction "TX0_P_7") (pintype "bidirectional"))
      (node (ref "U6") (pin "119") (pinfunction "HDMI_D0_P_119") (pintype "bidirectional"))
    )
    (net (code "22") (name "HDMI_D1_N") (class "Default")
      (node (ref "J7") (pin "6") (pinfunction "TX1_N_6") (pintype "bidirectional"))
      (node (ref "U6") (pin "123") (pinfunction "HDMI_D1_N_123") (pintype "bidirectional"))
    )
    (net (code "23") (name "HDMI_D1_P") (class "Default")
      (node (ref "J7") (pin "4") (pinfunction "TX1_P_4") (pintype "bidirectional"))
      (node (ref "U6") (pin "125") (pinfunction "HDMI_D1_P_125") (pintype "bidirectional"))
    )
    (net (code "24") (name "HDMI_D2_N") (class "Default")
      (node (ref "J7") (pin "3") (pinfunction "TX2_N_3") (pintype "bidirectional"))
      (node (ref "U6") (pin "129") (pinfunction "HDMI_D2_N_129") (pintype "bidirectional"))
    )
    (net (code "25") (name "HDMI_D2_P") (class "Default")
      (node (ref "J7") (pin "1") (pinfunction "TX2_P_1") (pintype "bidirectional"))
      (node (ref "U6") (pin "131") (pinfunction "HDMI_D2_P_131") (pintype "bidirectional"))
    )
    (net (code "26") (name "HDMI_HPD_N_1V8") (class "Default")
      (node (ref "Q5") (pin "D") (pinfunction "D_D") (pintype "passive"))
      (node (ref "R39") (pin "2") (pinfunction "22_2") (pintype "passive"))
      (node (ref "U6") (pin "88") (pinfunction "HDMI_HPD_N_1V8_88") (pintype "bidirectional"))
    )
    (net (code "27") (name "HDMI_SCL") (class "Default")
      (node (ref "J7") (pin "15") (pinfunction "SCL_15") (pintype "bidirectional"))
      (node (ref "U6") (pin "175") (pinfunction "HDMI_SCL_175") (pintype "bidirectional"))
      (node (ref "U7") (pin "A3") (pinfunction "SCL_A3") (pintype "bidirectional"))
    )
    (net (code "28") (name "HDMI_SDA") (class "Default")
      (node (ref "J7") (pin "16") (pinfunction "SDA_16") (pintype "bidirectional"))
      (node (ref "U6") (pin "173") (pinfunction "HDMI_SDA_173") (pintype "bidirectional"))
      (node (ref "U7") (pin "B3") (pinfunction "SDA_B3") (pintype "bidirectional"))
    )
    (net (code "29") (name "I2C_SCL") (class "Default")
      (node (ref "J11") (pin "4") (pinfunction "4_4") (pintype "bidirectional"))
      (node (ref "R6") (pin "2") (pinfunction "22_2") (pintype "passive"))
      (node (ref "U12") (pin "6") (pinfunction "SCL_6") (pintype "bidirectional"))
      (node (ref "U19") (pin "17") (pinfunction "SCLK_17") (pintype "bidirectional"))
      (node (ref "U2") (pin "13") (pinfunction "SCL_13") (pintype "input"))
      (node (ref "U6") (pin "11") (pinfunction "GPIO3_11") (pintype "bidirectional"))
    )
    (net (code "30") (name "I2C_SDA") (class "Default")
      (node (ref "J11") (pin "3") (pinfunction "3_3") (pintype "bidirectional"))
      (node (ref "R7") (pin "2") (pinfunction "22_2") (pintype "passive"))
      (node (ref "U12") (pin "2") (pinfunction "SDA_2") (pintype "bidirectional"))
      (node (ref "U19") (pin "18") (pinfunction "SDIN_18") (pintype "bidirectional"))
      (node (ref "U2") (pin "14") (pinfunction "SDA_14") (pintype "bidirectional"))
      (node (ref "U6") (pin "9") (pinfunction "GPIO2_9") (pintype "bidirectional"))
    )
    (net (code "31") (name "I2S_ADC") (class "Default")
      (node (ref "U19") (pin "16") (pinfunction "ADCDAT_16") (pintype "bidirectional"))
      (node (ref "U6") (pin "69") (pinfunction "GPIO20_69") (pintype "bidirectional"))
    )
    (net (code "32") (name "I2S_CLK") (class "Default")
      (node (ref "U19") (pin "12") (pinfunction "BCLK_12") (pintype "bidirectional"))
      (node (ref "U6") (pin "63") (pinfunction "GPIO18_63") (pintype "bidirectional"))
    )
    (net (code "33") (name "I2S_DAC") (class "Default")
      (node (ref "U19") (pin "14") (pinfunction "DACDAT_14") (pintype "bidirectional"))
      (node (ref "U6") (pin "71") (pinfunction "GPIO21_71") (pintype "bidirectional"))
    )
    (net (code "34") (name "I2S_LRCLK") (class "Default")
      (node (ref "U19") (pin "13") (pinfunction "DACLRC_13") (pintype "bidirectional"))
      (node (ref "U19") (pin "15") (pinfunction "ADCLRC/GPIO_15") (pintype "bidirectional"))
      (node (ref "U6") (pin "65") (pinfunction "GPIO19_65") (pintype "bidirectional"))
    )
    (net (code "35") (name "ID_SD") (class "Default")
      (node (ref "U18") (pin "CH_PD") (pinfunction "CH_PD_CH_PD") (pintype "bidirectional"))
      (node (ref "U6") (pin "3") (pinfunction "GPIO0_3") (pintype "bidirectional"))
    )
    (net (code "36") (name "IRQ") (class "Default")
      (node (ref "J2") (pin "4") (pinfunction "GPIO25_4") (pintype "bidirectional"))
      (node (ref "U6") (pin "70") (pinfunction "GPIO40_70") (pintype "bidirectional"))
    )
    (net (code "37") (name "ISET") (class "Default")
      (node (ref "JP2") (pin "2") (pinfunction "2_2") (pintype "passive"))
      (node (ref "U1") (pin "6") (pinfunction "ISET_6") (pintype "bidirectional"))
    )
    (net (code "38") (name "ITERM") (class "Default")
      (node (ref "R20") (pin "2") (pinfunction "22_2") (pintype "passive"))
      (node (ref "U1") (pin "10") (pinfunction "ITERM_10") (pintype "bidirectional"))
      (node (ref "U2") (pin "11") (pinfunction "AIN6_11") (pintype "input"))
    )
    (net (code "39") (name "J1_SW") (class "Default")
      (node (ref "J5") (pin "12") (pinfunction "12_12") (pintype "bidirectional"))
      (node (ref "U6") (pin "64") (pinfunction "GPIO38_64") (pintype "bidirectional"))
    )
    (net (code "40") (name "J2_SW") (class "Default")
      (node (ref "J10") (pin "18") (pinfunction "18_18") (pintype "bidirectional"))
      (node (ref "U6") (pin "66") (pinfunction "GPIO39_66") (pintype "bidirectional"))
    )
    (net (code "41") (name "LIN1") (class "Default")
      (node (ref "C38") (pin "2") (pinfunction "22_2") (pintype "passive"))
      (node (ref "U19") (pin "4") (pinfunction "LIN1_4") (pintype "bidirectional"))
    )
    (net (code "42") (name "MCLK") (class "Default")
      (node (ref "U19") (pin "11") (pinfunction "MCLK_11") (pintype "bidirectional"))
      (node (ref "Y1") (pin "3") (pinfunction "OUT_3") (pintype "bidirectional"))
    )
    (net (code "43") (name "MIC_OUTPUT") (class "Default")
      (node (ref "U2") (pin "10") (pinfunction "AIN5_10") (pintype "input"))
    )
    (net (code "44") (name "Net-(C27-22)") (class "Default")
      (node (ref "C27") (pin "2") (pinfunction "22_2") (pintype "passive"))
      (node (ref "FB5") (pin "2") (pinfunction "2_2") (pintype "passive"))
      (node (ref "MIC1") (pin "4") (pinfunction "OUT_4") (pintype "bidirectional"))
    )
    (net (code "45") (name "Net-(C28-22)") (class "Default")
      (node (ref "C28") (pin "2") (pinfunction "22_2") (pintype "passive"))
      (node (ref "C30") (pin "1") (pinfunction "11_1") (pintype "passive"))
      (node (ref "FB5") (pin "1") (pinfunction "1_1") (pintype "passive"))
    )
    (net (code "46") (name "Net-(C31-22)") (class "Default")
      (node (ref "C31") (pin "2") (pinfunction "22_2") (pintype "passive"))
      (node (ref "FB6") (pin "2") (pinfunction "2_2") (pintype "passive"))
      (node (ref "MIC2") (pin "4") (pinfunction "OUT_4") (pintype "bidirectional"))
    )
    (net (code "47") (name "Net-(C32-22)") (class "Default")
      (node (ref "C32") (pin "2") (pinfunction "22_2") (pintype "passive"))
      (node (ref "C38") (pin "1") (pinfunction "11_1") (pintype "passive"))
      (node (ref "FB6") (pin "1") (pinfunction "1_1") (pintype "passive"))
    )
    (net (code "48") (name "Net-(C39-22)") (class "Default")
      (node (ref "C39") (pin "2") (pinfunction "22_2") (pintype "passive"))
      (node (ref "FB3") (pin "2") (pinfunction "2_2") (pintype "passive"))
      (node (ref "LS1") (pin "1") (pinfunction "1_1") (pintype "passive"))
    )
    (net (code "49") (name "Net-(C40-22)") (class "Default")
      (node (ref "C40") (pin "2") (pinfunction "22_2") (pintype "passive"))
      (node (ref "FB4") (pin "2") (pinfunction "2_2") (pintype "passive"))
      (node (ref "LS1") (pin "2") (pinfunction "2_2") (pintype "passive"))
    )
    (net (code "50") (name "Net-(C53-22)") (class "Default")
      (node (ref "C53") (pin "2") (pinfunction "22_2") (pintype "passive"))
      (node (ref "FB1") (pin "2") (pinfunction "2_2") (pintype "passive"))
      (node (ref "U5") (pin "62") (pinfunction "VDD18USBPLL_62") (pintype "power_in"))
    )
    (net (code "51") (name "Net-(J3-VCC)") (class "Default")
      (node (ref "C1") (pin "2") (pinfunction "2_2") (pintype "passive"))
      (node (ref "C4") (pin "2") (pinfunction "2_2") (pintype "passive"))
      (node (ref "J3") (pin "1") (pinfunction "VCC_1") (pintype "power_in"))
      (node (ref "R1") (pin "2") (pinfunction "22_2") (pintype "passive"))
      (node (ref "R33") (pin "2") (pinfunction "22_2") (pintype "passive"))
      (node (ref "R41") (pin "1") (pinfunction "11_1") (pintype "passive"))
      (node (ref "U1") (pin "1") (pinfunction "VPIN_1") (pintype "power_in"))
    )
    (net (code "52") (name "Net-(J7-CEC_DAT)") (class "Default")
      (node (ref "J7") (pin "13") (pinfunction "CEC_DAT_13") (pintype "bidirectional"))
      (node (ref "Q6") (pin "D") (pinfunction "D_D") (pintype "passive"))
      (node (ref "U7") (pin "A2") (pinfunction "CEC_A2") (pintype "bidirectional"))
    )
    (net (code "53") (name "Net-(J7-HPD)") (class "Default")
      (node (ref "J7") (pin "19") (pinfunction "HPD_19") (pintype "bidirectional"))
      (node (ref "Q5") (pin "G") (pinfunction "G_G") (pintype "passive"))
      (node (ref "U7") (pin "C3") (pinfunction "HPD_C3") (pintype "bidirectional"))
    )
    (net (code "54") (name "Net-(L1-1)") (class "Default")
      (node (ref "L1") (pin "P$1") (pinfunction "1_P$1") (pintype "passive"))
      (node (ref "U3") (pin "B1") (pinfunction "SW_B1") (pintype "bidirectional"))
      (node (ref "U3") (pin "B2") (pinfunction "SW_B2") (pintype "bidirectional"))
    )
    (net (code "55") (name "Net-(L2-1)") (class "Default")
      (node (ref "L2") (pin "P$1") (pinfunction "1_P$1") (pintype "passive"))
      (node (ref "U10") (pin "1") (pinfunction "SW_1") (pintype "bidirectional"))
      (node (ref "U10") (pin "2") (pinfunction "SW_2") (pintype "bidirectional"))
    )
    (net (code "56") (name "Net-(L3-1)") (class "Default")
      (node (ref "L3") (pin "P$1") (pinfunction "1_P$1") (pintype "passive"))
      (node (ref "U16") (pin "1") (pinfunction "SW_1") (pintype "bidirectional"))
    )
    (net (code "57") (name "Net-(L5-1)") (class "Default")
      (node (ref "L5") (pin "P$1") (pinfunction "1_P$1") (pintype "passive"))
      (node (ref "U1") (pin "14") (pinfunction "LX_14") (pintype "bidirectional"))
    )
    (net (code "58") (name "Net-(L5-2)") (class "Default")
      (node (ref "L5") (pin "P$2") (pinfunction "2_P$2") (pintype "passive"))
      (node (ref "U1") (pin "13") (pinfunction "CS_13") (pintype "bidirectional"))
    )
    (net (code "59") (name "Net-(R1-11)") (class "Default")
      (node (ref "C3") (pin "2") (pinfunction "2_2") (pintype "passive"))
      (node (ref "R1") (pin "1") (pinfunction "11_1") (pintype "passive"))
      (node (ref "R2") (pin "1") (pinfunction "11_1") (pintype "passive"))
      (node (ref "U1") (pin "4") (pinfunction "VCC_4") (pintype "power_in"))
      (node (ref "U1") (pin "5") (pinfunction "EN_5") (pintype "bidirectional"))
    )
    (net (code "60") (name "Net-(R2-22)") (class "Default")
      (node (ref "R2") (pin "2") (pinfunction "22_2") (pintype "passive"))
      (node (ref "U1") (pin "11") (pinfunction "TS_11") (pintype "bidirectional"))
    )
    (net (code "61") (name "Net-(R3-22)") (class "Default")
      (node (ref "JP2") (pin "1") (pinfunction "1_1") (pintype "passive"))
      (node (ref "R3") (pin "2") (pinfunction "22_2") (pintype "passive"))
    )
    (net (code "62") (name "Net-(R8-11)") (class "Default")
      (node (ref "Q1") (pin "G") (pinfunction "G_G") (pintype "passive"))
      (node (ref "Q2") (pin "D") (pinfunction "D_D") (pintype "passive"))
      (node (ref "R8") (pin "1") (pinfunction "11_1") (pintype "passive"))
    )
    (net (code "63") (name "Net-(R11-11)") (class "Default")
      (node (ref "R11") (pin "1") (pinfunction "11_1") (pintype "passive"))
      (node (ref "U18") (pin "CS0") (pinfunction "CS0_CS0") (pintype "bidirectional"))
    )
    (net (code "64") (name "Net-(R12-11)") (class "Default")
      (node (ref "R12") (pin "1") (pinfunction "11_1") (pintype "passive"))
      (node (ref "U2") (pin "1") (pinfunction "REF_1") (pintype "bidirectional"))
    )
    (net (code "65") (name "Net-(R12-22)") (class "Default")
      (node (ref "R12") (pin "2") (pinfunction "22_2") (pintype "passive"))
      (node (ref "R13") (pin "1") (pinfunction "11_1") (pintype "passive"))
    )
    (net (code "66") (name "Net-(R13-22)") (class "Default")
      (node (ref "C10") (pin "1") (pinfunction "1_1") (pintype "passive"))
      (node (ref "R13") (pin "2") (pinfunction "22_2") (pintype "passive"))
    )
    (net (code "67") (name "Net-(R14-11)") (class "Default")
      (node (ref "R14") (pin "1") (pinfunction "11_1") (pintype "passive"))
      (node (ref "U18") (pin "MISO") (pinfunction "MISO_MISO") (pintype "bidirectional"))
    )
    (net (code "68") (name "Net-(R15-11)") (class "Default")
      (node (ref "R15") (pin "1") (pinfunction "11_1") (pintype "passive"))
      (node (ref "U18") (pin "GPIO9") (pinfunction "*GPIO9_GPIO9") (pintype "bidirectional"))
    )
    (net (code "69") (name "Net-(R16-11)") (class "Default")
      (node (ref "R16") (pin "1") (pinfunction "11_1") (pintype "passive"))
      (node (ref "R9") (pin "2") (pinfunction "22_2") (pintype "passive"))
      (node (ref "U2") (pin "5") (pinfunction "AIN0_5") (pintype "input"))
    )
    (net (code "70") (name "Net-(R17-22)") (class "Default")
      (node (ref "D2") (pin "C") (pinfunction "C_C") (pintype "passive"))
      (node (ref "R17") (pin "2") (pinfunction "22_2") (pintype "passive"))
    )
    (net (code "71") (name "Net-(R18-22)") (class "Default")
      (node (ref "D3") (pin "C") (pinfunction "C_C") (pintype "passive"))
      (node (ref "R18") (pin "2") (pinfunction "22_2") (pintype "passive"))
    )
    (net (code "72") (name "Net-(R19-22)") (class "Default")
      (node (ref "JP2") (pin "3") (pinfunction "3_3") (pintype "passive"))
      (node (ref "R19") (pin "2") (pinfunction "22_2") (pintype "passive"))
    )
    (net (code "73") (name "Net-(R21-11)") (class "Default")
      (node (ref "R21") (pin "1") (pinfunction "11_1") (pintype "passive"))
      (node (ref "U18") (pin "GPIO10") (pinfunction "*GPIO10_GPIO10") (pintype "bidirectional"))
    )
    (net (code "74") (name "Net-(R23-22)") (class "Default")
      (node (ref "R23") (pin "2") (pinfunction "22_2") (pintype "passive"))
      (node (ref "R5") (pin "1") (pinfunction "11_1") (pintype "passive"))
      (node (ref "U8") (pin "A") (pinfunction "A_A") (pintype "bidirectional"))
    )
    (net (code "75") (name "Net-(R24-11)") (class "Default")
      (node (ref "R24") (pin "1") (pinfunction "11_1") (pintype "passive"))
      (node (ref "R25") (pin "2") (pinfunction "22_2") (pintype "passive"))
      (node (ref "U8") (pin "B") (pinfunction "B_B") (pintype "bidirectional"))
    )
    (net (code "76") (name "Net-(R26-22)") (class "Default")
      (node (ref "R26") (pin "2") (pinfunction "22_2") (pintype "passive"))
      (node (ref "R27") (pin "1") (pinfunction "11_1") (pintype "passive"))
      (node (ref "U9") (pin "A") (pinfunction "A_A") (pintype "bidirectional"))
    )
    (net (code "77") (name "Net-(R28-11)") (class "Default")
      (node (ref "R28") (pin "1") (pinfunction "11_1") (pintype "passive"))
      (node (ref "R29") (pin "2") (pinfunction "22_2") (pintype "passive"))
      (node (ref "U9") (pin "B") (pinfunction "B_B") (pintype "bidirectional"))
    )
    (net (code "78") (name "Net-(R30-11)") (class "Default")
      (node (ref "R30") (pin "1") (pinfunction "11_1") (pintype "passive"))
      (node (ref "U18") (pin "MOSI") (pinfunction "MOSI_MOSI") (pintype "bidirectional"))
    )
    (net (code "79") (name "Net-(R31-11)") (class "Default")
      (node (ref "R31") (pin "1") (pinfunction "11_1") (pintype "passive"))
      (node (ref "U18") (pin "SCLK") (pinfunction "SCLK_SCLK") (pintype "bidirectional"))
    )
    (net (code "80") (name "Net-(R32-11)") (class "Default")
      (node (ref "D1") (pin "A") (pinfunction "A_A") (pintype "passive"))
      (node (ref "R32") (pin "1") (pinfunction "11_1") (pintype "passive"))
    )
    (net (code "81") (name "Net-(R33-11)") (class "Default")
      (node (ref "D4") (pin "A") (pinfunction "A_A") (pintype "passive"))
      (node (ref "R33") (pin "1") (pinfunction "11_1") (pintype "passive"))
    )
    (net (code "82") (name "Net-(R45-11)") (class "Default")
      (node (ref "R45") (pin "1") (pinfunction "11_1") (pintype "passive"))
      (node (ref "U6") (pin "168") (pinfunction "USB_OTGID_168") (pintype "bidirectional"))
    )
    (net (code "83") (name "Net-(R48-22)") (class "Default")
      (node (ref "R48") (pin "2") (pinfunction "22_2") (pintype "passive"))
      (node (ref "U10") (pin "13") (pinfunction "EN_13") (pintype "bidirectional"))
      (node (ref "U11") (pin "6") (pinfunction "FLAG1_6") (pintype "passive"))
    )
    (net (code "84") (name "Net-(R49-22)") (class "Default")
      (node (ref "R49") (pin "2") (pinfunction "22_2") (pintype "passive"))
      (node (ref "U11") (pin "5") (pinfunction "FLAG2_5") (pintype "passive"))
      (node (ref "U16") (pin "2") (pinfunction "EN_2") (pintype "bidirectional"))
    )
    (net (code "85") (name "Net-(R50-11)") (class "Default")
      (node (ref "R50") (pin "1") (pinfunction "11_1") (pintype "passive"))
      (node (ref "U5") (pin "63") (pinfunction "USBRBIAS_63") (pintype "input"))
    )
    (net (code "86") (name "Net-(R51-11)") (class "Default")
      (node (ref "R51") (pin "1") (pinfunction "11_1") (pintype "passive"))
      (node (ref "U5") (pin "41") (pinfunction "AUTOMDIX_EN_41") (pintype "input"))
    )
    (net (code "87") (name "Net-(R52-22)") (class "Default")
      (node (ref "R52") (pin "2") (pinfunction "22_2") (pintype "passive"))
      (node (ref "U5") (pin "50") (pinfunction "EXRES_50") (pintype "input"))
    )
    (net (code "88") (name "Net-(U1-CT)") (class "Default")
      (node (ref "C2") (pin "2") (pinfunction "2_2") (pintype "passive"))
      (node (ref "U1") (pin "7") (pinfunction "CT_7") (pintype "bidirectional"))
    )
    (net (code "89") (name "Net-(U2-AIN1)") (class "Default")
      (node (ref "J5") (pin "13") (pinfunction "13_13") (pintype "bidirectional"))
      (node (ref "U2") (pin "6") (pinfunction "AIN1_6") (pintype "input"))
    )
    (net (code "90") (name "Net-(U2-AIN2)") (class "Default")
      (node (ref "J5") (pin "14") (pinfunction "14_14") (pintype "bidirectional"))
      (node (ref "U2") (pin "7") (pinfunction "AIN2_7") (pintype "input"))
    )
    (net (code "91") (name "Net-(U2-AIN3)") (class "Default")
      (node (ref "J10") (pin "19") (pinfunction "19_19") (pintype "bidirectional"))
      (node (ref "U2") (pin "8") (pinfunction "AIN3_8") (pintype "input"))
    )
    (net (code "92") (name "Net-(U2-AIN4)") (class "Default")
      (node (ref "J10") (pin "20") (pinfunction "20_20") (pintype "bidirectional"))
      (node (ref "U2") (pin "9") (pinfunction "AIN4_9") (pintype "input"))
    )
    (net (code "93") (name "Net-(U5B-VDD18CORE)") (class "Default")
      (node (ref "C54") (pin "2") (pinfunction "2_2") (pintype "passive"))
      (node (ref "C66") (pin "2") (pinfunction "2_2") (pintype "passive"))
      (node (ref "C67") (pin "2") (pinfunction "2_2") (pintype "passive"))
      (node (ref "U5") (pin "15") (pinfunction "VDD18CORE_2_15") (pintype "power_in"))
      (node (ref "U5") (pin "38") (pinfunction "VDD18CORE_38") (pintype "power_in"))
    )
    (net (code "94") (name "Net-(U5B-VDD18ETHPLL)") (class "Default")
      (node (ref "C65") (pin "2") (pinfunction "2_2") (pintype "passive"))
      (node (ref "FB1") (pin "1") (pinfunction "1_1") (pintype "passive"))
      (node (ref "U5") (pin "48") (pinfunction "VDD18ETHPLL_48") (pintype "power_in"))
    )
    (net (code "95") (name "Net-(U6-GPIO4)") (class "Default")
      (node (ref "J8") (pin "1") (pinfunction "1_1") (pintype "bidirectional"))
      (node (ref "U6") (pin "15") (pinfunction "GPIO4_15") (pintype "bidirectional"))
    )
    (net (code "96") (name "Net-(U10-CN)") (class "Default")
      (node (ref "C6") (pin "1") (pinfunction "1_1") (pintype "bidirectional"))
      (node (ref "U10") (pin "8") (pinfunction "CN_8") (pintype "bidirectional"))
    )
    (net (code "97") (name "Net-(U10-CP)") (class "Default")
      (node (ref "C6") (pin "2") (pinfunction "2_2") (pintype "bidirectional"))
      (node (ref "U10") (pin "7") (pinfunction "CP_7") (pintype "bidirectional"))
    )
    (net (code "98") (name "Net-(U10-SS)") (class "Default")
      (node (ref "C7") (pin "2") (pinfunction "2_2") (pintype "bidirectional"))
      (node (ref "U10") (pin "9") (pinfunction "SS_9") (pintype "bidirectional"))
    )
    (net (code "99") (name "Net-(U16-CFF)") (class "Default")
      (node (ref "C18") (pin "1") (pinfunction "1_1") (pintype "passive"))
      (node (ref "U16") (pin "5") (pinfunction "CFF_5") (pintype "bidirectional"))
    )
    (net (code "100") (name "Net-(U17-(PCINT0{slash}TPIDATA)_PB0)") (class "Default")
      (node (ref "TP2") (pin "TP") (pinfunction "TP_TP") (pintype "input"))
      (node (ref "U17") (pin "1") (pinfunction "(PCINT0/TPIDATA)_PB0_1") (pintype "bidirectional"))
    )
    (net (code "101") (name "Net-(U17-PB3_(~{RESET}))") (class "Default")
      (node (ref "TP1") (pin "TP") (pinfunction "TP_TP") (pintype "input"))
      (node (ref "U17") (pin "6") (pinfunction "PB3_(~{RESET})_6") (pintype "bidirectional"))
    )
    (net (code "102") (name "Net-(U19-SPK_RN)") (class "Default")
      (node (ref "FB4") (pin "1") (pinfunction "1_1") (pintype "passive"))
      (node (ref "U19") (pin "19") (pinfunction "SPK_RN_19") (pintype "bidirectional"))
    )
    (net (code "103") (name "Net-(U19-SPK_RP)") (class "Default")
      (node (ref "FB3") (pin "1") (pinfunction "1_1") (pintype "passive"))
      (node (ref "U19") (pin "22") (pinfunction "SPK_RP_22") (pintype "bidirectional"))
    )
    (net (code "104") (name "Net-(U19-VMID)") (class "Default")
      (node (ref "C25") (pin "1") (pinfunction "1_1") (pintype "passive"))
      (node (ref "C26") (pin "1") (pinfunction "1_1") (pintype "passive"))
      (node (ref "U19") (pin "27") (pinfunction "VMID_27") (pintype "bidirectional"))
    )
    (net (code "105") (name "POWER_SEQ_EN") (class "Default")
      (node (ref "R4") (pin "2") (pinfunction "22_2") (pintype "passive"))
      (node (ref "U11") (pin "3") (pinfunction "EN_3") (pintype "input"))
    )
    (net (code "106") (name "RIN1") (class "Default")
      (node (ref "C30") (pin "2") (pinfunction "22_2") (pintype "passive"))
      (node (ref "U19") (pin "5") (pinfunction "RIN1_5") (pintype "bidirectional"))
    )
    (net (code "107") (name "RX_N") (class "Default")
      (node (ref "J10") (pin "15") (pinfunction "15_15") (pintype "bidirectional"))
      (node (ref "U5") (pin "53") (pinfunction "RXN_53") (pintype "bidirectional"))
    )
    (net (code "108") (name "RX_P") (class "Default")
      (node (ref "J10") (pin "16") (pinfunction "16_16") (pintype "bidirectional"))
      (node (ref "U5") (pin "52") (pinfunction "RXP_52") (pintype "bidirectional"))
    )
    (net (code "109") (name "SDX_CLK") (class "Default")
      (node (ref "U$2") (pin "5") (pinfunction "CLK_5") (pintype "bidirectional"))
      (node (ref "U6") (pin "10") (pinfunction "SDX_CLK_10") (pintype "bidirectional"))
    )
    (net (code "110") (name "SDX_CMD") (class "Default")
      (node (ref "U$2") (pin "3") (pinfunction "CMD_3") (pintype "bidirectional"))
      (node (ref "U6") (pin "12") (pinfunction "SDX_CMD_12") (pintype "bidirectional"))
    )
    (net (code "111") (name "SDX_D0") (class "Default")
      (node (ref "U$2") (pin "7") (pinfunction "DAT0_7") (pintype "bidirectional"))
      (node (ref "U6") (pin "16") (pinfunction "SDX_D0_16") (pintype "bidirectional"))
    )
    (net (code "112") (name "SDX_D1") (class "Default")
      (node (ref "U$2") (pin "8") (pinfunction "DAT1_8") (pintype "bidirectional"))
      (node (ref "U6") (pin "18") (pinfunction "SDX_D1_18") (pintype "bidirectional"))
    )
    (net (code "113") (name "SDX_D2") (class "Default")
      (node (ref "U$2") (pin "1") (pinfunction "DAT2_1") (pintype "bidirectional"))
      (node (ref "U6") (pin "22") (pinfunction "SDX_D2_22") (pintype "bidirectional"))
    )
    (net (code "114") (name "SDX_D3") (class "Default")
      (node (ref "U$2") (pin "2") (pinfunction "CD/DAT3_2") (pintype "bidirectional"))
      (node (ref "U6") (pin "24") (pinfunction "SDX_D3_24") (pintype "bidirectional"))
    )
    (net (code "115") (name "SD_CLK") (class "Default")
      (node (ref "R31") (pin "2") (pinfunction "22_2") (pintype "passive"))
      (node (ref "U6") (pin "75") (pinfunction "GPIO22_75") (pintype "bidirectional"))
    )
    (net (code "116") (name "SD_CMD") (class "Default")
      (node (ref "R11") (pin "2") (pinfunction "22_2") (pintype "passive"))
      (node (ref "U6") (pin "77") (pinfunction "GPIO23_77") (pintype "bidirectional"))
    )
    (net (code "117") (name "SD_D0") (class "Default")
      (node (ref "R14") (pin "2") (pinfunction "22_2") (pintype "passive"))
      (node (ref "U6") (pin "81") (pinfunction "GPIO24_81") (pintype "bidirectional"))
    )
    (net (code "118") (name "SD_D1") (class "Default")
      (node (ref "R30") (pin "2") (pinfunction "22_2") (pintype "passive"))
      (node (ref "U6") (pin "83") (pinfunction "GPIO25_83") (pintype "bidirectional"))
    )
    (net (code "119") (name "SD_D2") (class "Default")
      (node (ref "R15") (pin "2") (pinfunction "22_2") (pintype "passive"))
      (node (ref "U6") (pin "87") (pinfunction "GPIO26_87") (pintype "bidirectional"))
    )
    (net (code "120") (name "SD_D3") (class "Default")
      (node (ref "R21") (pin "2") (pinfunction "22_2") (pintype "passive"))
      (node (ref "U6") (pin "89") (pinfunction "GPIO27_89") (pintype "bidirectional"))
    )
    (net (code "121") (name "SHUTDOWN_SIG") (class "Default")
      (node (ref "R43") (pin "1") (pinfunction "11_1") (pintype "passive"))
      (node (ref "U17") (pin "4") (pinfunction "PB2_(T0/CLKO/PCINT2)_4") (pintype "bidirectional"))
      (node (ref "U6") (pin "17") (pinfunction "GPIO5_17") (pintype "bidirectional"))
    )
    (net (code "122") (name "SPI_CS0") (class "Default")
      (node (ref "J2") (pin "5") (pinfunction "CS0_5") (pintype "bidirectional"))
      (node (ref "U6") (pin "27") (pinfunction "GPIO8_27") (pintype "bidirectional"))
    )
    (net (code "123") (name "SPI_CS1") (class "Default")
      (node (ref "J2") (pin "6") (pinfunction "CS1_6") (pintype "bidirectional"))
      (node (ref "U6") (pin "23") (pinfunction "GPIO7_23") (pintype "bidirectional"))
    )
    (net (code "124") (name "SPI_MISO") (class "Default")
      (node (ref "J2") (pin "9") (pinfunction "MISO_9") (pintype "bidirectional"))
      (node (ref "U6") (pin "29") (pinfunction "GPIO9_29") (pintype "bidirectional"))
    )
    (net (code "125") (name "SPI_MOSI") (class "Default")
      (node (ref "J2") (pin "10") (pinfunction "MOSI_10") (pintype "bidirectional"))
      (node (ref "U6") (pin "33") (pinfunction "GPIO10_33") (pintype "bidirectional"))
    )
    (net (code "126") (name "SPI_SCLK") (class "Default")
      (node (ref "J2") (pin "8") (pinfunction "SCLK_8") (pintype "bidirectional"))
      (node (ref "U6") (pin "35") (pinfunction "GPIO11_35") (pintype "bidirectional"))
    )
    (net (code "127") (name "STAT1") (class "Default")
      (node (ref "R17") (pin "1") (pinfunction "11_1") (pintype "passive"))
      (node (ref "U1") (pin "9") (pinfunction "STAT1_9") (pintype "bidirectional"))
      (node (ref "U6") (pin "46") (pinfunction "GPIO32_46") (pintype "bidirectional"))
    )
    (net (code "128") (name "STAT2") (class "Default")
      (node (ref "R18") (pin "1") (pinfunction "11_1") (pintype "passive"))
      (node (ref "U1") (pin "8") (pinfunction "STAT2_8") (pintype "bidirectional"))
      (node (ref "U6") (pin "48") (pinfunction "GPIO33_48") (pintype "bidirectional"))
    )
    (net (code "129") (name "SWITCH_IN") (class "Default")
      (node (ref "C5") (pin "2") (pinfunction "2_2") (pintype "passive"))
      (node (ref "J4") (pin "2") (pinfunction "2_2") (pintype "bidirectional"))
      (node (ref "J6") (pin "1") (pinfunction "5V_1") (pintype "power_in"))
      (node (ref "Q1") (pin "S") (pinfunction "S_S") (pintype "passive"))
      (node (ref "R8") (pin "2") (pinfunction "22_2") (pintype "passive"))
      (node (ref "R9") (pin "1") (pinfunction "11_1") (pintype "passive"))
      (node (ref "U1") (pin "12") (pinfunction "BAT_12") (pintype "power_in"))
    )
    (net (code "130") (name "SWITCH_OUT") (class "Default")
      (node (ref "D6") (pin "A") (pinfunction "21_A") (pintype "passive"))
      (node (ref "J4") (pin "3") (pinfunction "3_3") (pintype "bidirectional"))
      (node (ref "U6") (pin "21") (pinfunction "GPIO6_21") (pintype "bidirectional"))
    )
    (net (code "131") (name "TX_N") (class "Default")
      (node (ref "J10") (pin "12") (pinfunction "12_12") (pintype "bidirectional"))
      (node (ref "U5") (pin "56") (pinfunction "TXN_56") (pintype "bidirectional"))
    )
    (net (code "132") (name "TX_P") (class "Default")
      (node (ref "J10") (pin "13") (pinfunction "13_13") (pintype "bidirectional"))
      (node (ref "U5") (pin "55") (pinfunction "TXP_55") (pintype "bidirectional"))
    )
    (net (code "133") (name "UART_RX") (class "Default")
      (node (ref "J1") (pin "2") (pinfunction "2_2") (pintype "bidirectional"))
      (node (ref "U6") (pin "53") (pinfunction "GPIO15_53") (pintype "bidirectional"))
    )
    (net (code "134") (name "UART_TX") (class "Default")
      (node (ref "J1") (pin "1") (pinfunction "1_1") (pintype "bidirectional"))
      (node (ref "U6") (pin "51") (pinfunction "GPIO14_51") (pintype "bidirectional"))
    )
    (net (code "135") (name "USB_D2_N") (class "Default")
      (node (ref "J9") (pin "2") (pinfunction "D-_2") (pintype "bidirectional"))
      (node (ref "U5") (pin "1") (pinfunction "USBDM2_1") (pintype "bidirectional"))
    )
    (net (code "136") (name "USB_D2_P") (class "Default")
      (node (ref "J9") (pin "3") (pinfunction "D+_3") (pintype "bidirectional"))
      (node (ref "U5") (pin "2") (pinfunction "USBDP2_2") (pintype "bidirectional"))
    )
    (net (code "137") (name "USB_D3_N") (class "Default")
      (node (ref "U5") (pin "3") (pinfunction "USBDM3_3") (pintype "bidirectional"))
    )
    (net (code "138") (name "USB_D3_P") (class "Default")
      (node (ref "U5") (pin "4") (pinfunction "USBDP3_4") (pintype "bidirectional"))
    )
    (net (code "139") (name "USB_D_N") (class "Default")
      (node (ref "U5") (pin "58") (pinfunction "USBDM0_58") (pintype "bidirectional"))
      (node (ref "U6") (pin "167") (pinfunction "USB_DM_167") (pintype "bidirectional"))
    )
    (net (code "140") (name "USB_D_P") (class "Default")
      (node (ref "U5") (pin "59") (pinfunction "USBDP0_59") (pintype "bidirectional"))
      (node (ref "U6") (pin "165") (pinfunction "USB_DP_165") (pintype "bidirectional"))
    )
    (net (code "141") (name "unconnected-(J3-D+-Pad3)") (class "Default")
      (node (ref "J3") (pin "3") (pinfunction "D+_3") (pintype "bidirectional"))
    )
    (net (code "142") (name "unconnected-(J3-D--Pad2)") (class "Default")
      (node (ref "J3") (pin "2") (pinfunction "D-_2") (pintype "bidirectional"))
    )
    (net (code "143") (name "unconnected-(J5-Pad1)") (class "Default")
      (node (ref "J5") (pin "1") (pinfunction "1_1") (pintype "bidirectional"))
    )
    (net (code "144") (name "unconnected-(J5-Pad2)") (class "Default")
      (node (ref "J5") (pin "2") (pinfunction "2_2") (pintype "bidirectional"))
    )
    (net (code "145") (name "unconnected-(J5-Pad3)") (class "Default")
      (node (ref "J5") (pin "3") (pinfunction "3_3") (pintype "bidirectional"))
    )
    (net (code "146") (name "unconnected-(J5-Pad4)") (class "Default")
      (node (ref "J5") (pin "4") (pinfunction "4_4") (pintype "bidirectional"))
    )
    (net (code "147") (name "unconnected-(J5-Pad5)") (class "Default")
      (node (ref "J5") (pin "5") (pinfunction "5_5") (pintype "bidirectional"))
    )
    (net (code "148") (name "unconnected-(J5-Pad6)") (class "Default")
      (node (ref "J5") (pin "6") (pinfunction "6_6") (pintype "bidirectional"))
    )
    (net (code "149") (name "unconnected-(J5-Pad7)") (class "Default")
      (node (ref "J5") (pin "7") (pinfunction "7_7") (pintype "bidirectional"))
    )
    (net (code "150") (name "unconnected-(J5-Pad8)") (class "Default")
      (node (ref "J5") (pin "8") (pinfunction "8_8") (pintype "bidirectional"))
    )
    (net (code "151") (name "unconnected-(J5-Pad9)") (class "Default")
      (node (ref "J5") (pin "9") (pinfunction "9_9") (pintype "bidirectional"))
    )
    (net (code "152") (name "unconnected-(J5-Pad10)") (class "Default")
      (node (ref "J5") (pin "10") (pinfunction "10_10") (pintype "bidirectional"))
    )
    (net (code "153") (name "unconnected-(J5-Pad16)") (class "Default")
      (node (ref "J5") (pin "16") (pinfunction "16_16") (pintype "bidirectional"))
    )
    (net (code "154") (name "unconnected-(J5-Pad17)") (class "Default")
      (node (ref "J5") (pin "17") (pinfunction "17_17") (pintype "bidirectional"))
    )
    (net (code "155") (name "unconnected-(J5-Pad18)") (class "Default")
      (node (ref "J5") (pin "18") (pinfunction "18_18") (pintype "bidirectional"))
    )
    (net (code "156") (name "unconnected-(J5-Pad19)") (class "Default")
      (node (ref "J5") (pin "19") (pinfunction "19_19") (pintype "bidirectional"))
    )
    (net (code "157") (name "unconnected-(J5-Pad20)") (class "Default")
      (node (ref "J5") (pin "20") (pinfunction "20_20") (pintype "bidirectional"))
    )
    (net (code "158") (name "unconnected-(J7-+5V-Pad18)") (class "Default")
      (node (ref "J7") (pin "18") (pinfunction "+5V_18") (pintype "bidirectional"))
    )
    (net (code "159") (name "unconnected-(J7-NC-Pad14)") (class "Default")
      (node (ref "J7") (pin "14") (pinfunction "NC_14") (pintype "bidirectional"))
    )
    (net (code "160") (name "unconnected-(J10-Pad3)") (class "Default")
      (node (ref "J10") (pin "3") (pinfunction "3_3") (pintype "bidirectional"))
    )
    (net (code "161") (name "unconnected-(J10-Pad4)") (class "Default")
      (node (ref "J10") (pin "4") (pinfunction "4_4") (pintype "bidirectional"))
    )
    (net (code "162") (name "unconnected-(J10-Pad5)") (class "Default")
      (node (ref "J10") (pin "5") (pinfunction "5_5") (pintype "bidirectional"))
    )
    (net (code "163") (name "unconnected-(J10-Pad6)") (class "Default")
      (node (ref "J10") (pin "6") (pinfunction "6_6") (pintype "bidirectional"))
    )
    (net (code "164") (name "unconnected-(J10-Pad7)") (class "Default")
      (node (ref "J10") (pin "7") (pinfunction "7_7") (pintype "bidirectional"))
    )
    (net (code "165") (name "unconnected-(J10-Pad8)") (class "Default")
      (node (ref "J10") (pin "8") (pinfunction "8_8") (pintype "bidirectional"))
    )
    (net (code "166") (name "unconnected-(J10-Pad9)") (class "Default")
      (node (ref "J10") (pin "9") (pinfunction "9_9") (pintype "bidirectional"))
    )
    (net (code "167") (name "unconnected-(J10-Pad10)") (class "Default")
      (node (ref "J10") (pin "10") (pinfunction "10_10") (pintype "bidirectional"))
    )
    (net (code "168") (name "unconnected-(U2-AIN7-Pad12)") (class "Default")
      (node (ref "U2") (pin "12") (pinfunction "AIN7_12") (pintype "input"))
    )
    (net (code "169") (name "unconnected-(U2-NC-Pad4)") (class "Default")
      (node (ref "U2") (pin "4") (pinfunction "NC_4") (pintype "no_connect"))
    )
    (net (code "170") (name "unconnected-(U2-NC_2-Pad2)") (class "Default")
      (node (ref "U2") (pin "2") (pinfunction "NC_2_2") (pintype "no_connect"))
    )
    (net (code "171") (name "unconnected-(U2-NC_3-Pad3)") (class "Default")
      (node (ref "U2") (pin "3") (pinfunction "NC_3_3") (pintype "no_connect"))
    )
    (net (code "172") (name "unconnected-(U3-BP-PadC3)") (class "Default")
      (node (ref "U3") (pin "C3") (pinfunction "BP_C3") (pintype "input"))
    )
    (net (code "173") (name "unconnected-(U5A-CLK24_OUT-Pad45)") (class "Default")
      (node (ref "U5") (pin "45") (pinfunction "CLK24_OUT_45") (pintype "output"))
    )
    (net (code "174") (name "unconnected-(U5A-EECLK-Pad23)") (class "Default")
      (node (ref "U5") (pin "23") (pinfunction "EECLK_23") (pintype "output"))
    )
    (net (code "175") (name "unconnected-(U5A-EECS-Pad24)") (class "Default")
      (node (ref "U5") (pin "24") (pinfunction "EECS_24") (pintype "output"))
    )
    (net (code "176") (name "unconnected-(U5A-EEDI-Pad26)") (class "Default")
      (node (ref "U5") (pin "26") (pinfunction "EEDI_26") (pintype "input"))
    )
    (net (code "177") (name "unconnected-(U5A-EEDO-Pad25)") (class "Default")
      (node (ref "U5") (pin "25") (pinfunction "EEDO_25") (pintype "output"))
    )
    (net (code "178") (name "unconnected-(U5A-GPIO3-Pad35)") (class "Default")
      (node (ref "U5") (pin "35") (pinfunction "GPIO3_35") (pintype "bidirectional"))
    )
    (net (code "179") (name "unconnected-(U5A-GPIO4-Pad36)") (class "Default")
      (node (ref "U5") (pin "36") (pinfunction "GPIO4_36") (pintype "bidirectional"))
    )
    (net (code "180") (name "unconnected-(U5A-GPIO5-Pad37)") (class "Default")
      (node (ref "U5") (pin "37") (pinfunction "GPIO5_37") (pintype "bidirectional"))
    )
    (net (code "181") (name "unconnected-(U5A-GPIO6-Pad42)") (class "Default")
      (node (ref "U5") (pin "42") (pinfunction "GPIO6_42") (pintype "bidirectional"))
    )
    (net (code "182") (name "unconnected-(U5A-GPIO7-Pad43)") (class "Default")
      (node (ref "U5") (pin "43") (pinfunction "GPIO7_43") (pintype "bidirectional"))
    )
    (net (code "183") (name "unconnected-(U5A-NFDX_LED{slash}GPIO0-Pad20)") (class "Default")
      (node (ref "U5") (pin "20") (pinfunction "NFDX_LED/GPIO0_20") (pintype "bidirectional"))
    )
    (net (code "184") (name "unconnected-(U5A-NLNKA_LED{slash}GPIO1-Pad21)") (class "Default")
      (node (ref "U5") (pin "21") (pinfunction "NLNKA_LED/GPIO1_21") (pintype "bidirectional"))
    )
    (net (code "185") (name "unconnected-(U5A-NRESET-Pad12)") (class "Default")
      (node (ref "U5") (pin "12") (pinfunction "NRESET_12") (pintype "input"))
    )
    (net (code "186") (name "unconnected-(U5A-NSPD_LED{slash}GPIO2-Pad22)") (class "Default")
      (node (ref "U5") (pin "22") (pinfunction "NSPD_LED/GPIO2_22") (pintype "bidirectional"))
    )
    (net (code "187") (name "unconnected-(U5A-NTRST-Pad28)") (class "Default")
      (node (ref "U5") (pin "28") (pinfunction "NTRST_28") (pintype "input"))
    )
    (net (code "188") (name "unconnected-(U5A-PRTCTL3-Pad16)") (class "Default")
      (node (ref "U5") (pin "16") (pinfunction "PRTCTL3_16") (pintype "bidirectional"))
    )
    (net (code "189") (name "unconnected-(U5A-PRTXTL2-Pad14)") (class "Default")
      (node (ref "U5") (pin "14") (pinfunction "PRTXTL2_14") (pintype "bidirectional"))
    )
    (net (code "190") (name "unconnected-(U5A-TCK-Pad32)") (class "Default")
      (node (ref "U5") (pin "32") (pinfunction "TCK_32") (pintype "input"))
    )
    (net (code "191") (name "unconnected-(U5A-TDI-Pad30)") (class "Default")
      (node (ref "U5") (pin "30") (pinfunction "TDI_30") (pintype "input"))
    )
    (net (code "192") (name "unconnected-(U5A-TDO-Pad31)") (class "Default")
      (node (ref "U5") (pin "31") (pinfunction "TDO_31") (pintype "output"))
    )
    (net (code "193") (name "unconnected-(U5A-TEST1-Pad13)") (class "Default")
      (node (ref "U5") (pin "13") (pinfunction "TEST1_13") (pintype "passive"))
    )
    (net (code "194") (name "unconnected-(U5A-TEST4-Pad47)") (class "Default")
      (node (ref "U5") (pin "47") (pinfunction "TEST4_47") (pintype "passive"))
    )
    (net (code "195") (name "unconnected-(U5A-TMS-Pad29)") (class "Default")
      (node (ref "U5") (pin "29") (pinfunction "TMS_29") (pintype "input"))
    )
    (net (code "196") (name "unconnected-(U5A-XO-Pad60)") (class "Default")
      (node (ref "U5") (pin "60") (pinfunction "XO_60") (pintype "output"))
    )
    (net (code "197") (name "unconnected-(U5B-NC-Pad18)") (class "Default")
      (node (ref "U5") (pin "18") (pinfunction "NC_18") (pintype "no_connect"))
    )
    (net (code "198") (name "unconnected-(U5B-NC_2-Pad6)") (class "Default")
      (node (ref "U5") (pin "6") (pinfunction "NC_2_6") (pintype "no_connect"))
    )
    (net (code "199") (name "unconnected-(U5B-NC_3-Pad7)") (class "Default")
      (node (ref "U5") (pin "7") (pinfunction "NC_3_7") (pintype "no_connect"))
    )
    (net (code "200") (name "unconnected-(U5B-NC_4-Pad8)") (class "Default")
      (node (ref "U5") (pin "8") (pinfunction "NC_4_8") (pintype "no_connect"))
    )
    (net (code "201") (name "unconnected-(U5B-NC_5-Pad9)") (class "Default")
      (node (ref "U5") (pin "9") (pinfunction "NC_5_9") (pintype "no_connect"))
    )
    (net (code "202") (name "unconnected-(U5B-NC_6-Pad17)") (class "Default")
      (node (ref "U5") (pin "17") (pinfunction "NC_6_17") (pintype "no_connect"))
    )
    (net (code "203") (name "unconnected-(U6-CAM0_CN-Pad144)") (class "Default")
      (node (ref "U6") (pin "144") (pinfunction "CAM0_CN_144") (pintype "bidirectional"))
    )
    (net (code "204") (name "unconnected-(U6-CAM0_CP-Pad142)") (class "Default")
      (node (ref "U6") (pin "142") (pinfunction "CAM0_CP_142") (pintype "bidirectional"))
    )
    (net (code "205") (name "unconnected-(U6-CAM0_DN0-Pad138)") (class "Default")
      (node (ref "U6") (pin "138") (pinfunction "CAM0_DN0_138") (pintype "bidirectional"))
    )
    (net (code "206") (name "unconnected-(U6-CAM0_DN1-Pad150)") (class "Default")
      (node (ref "U6") (pin "150") (pinfunction "CAM0_DN1_150") (pintype "bidirectional"))
    )
    (net (code "207") (name "unconnected-(U6-CAM0_DP0-Pad136)") (class "Default")
      (node (ref "U6") (pin "136") (pinfunction "CAM0_DP0_136") (pintype "bidirectional"))
    )
    (net (code "208") (name "unconnected-(U6-CAM0_DP1-Pad148)") (class "Default")
      (node (ref "U6") (pin "148") (pinfunction "CAM0_DP1_148") (pintype "bidirectional"))
    )
    (net (code "209") (name "unconnected-(U6-CAM1_CN-Pad149)") (class "Default")
      (node (ref "U6") (pin "149") (pinfunction "CAM1_CN_149") (pintype "bidirectional"))
    )
    (net (code "210") (name "unconnected-(U6-CAM1_CP-Pad147)") (class "Default")
      (node (ref "U6") (pin "147") (pinfunction "CAM1_CP_147") (pintype "bidirectional"))
    )
    (net (code "211") (name "unconnected-(U6-CAM1_DN0-Pad161)") (class "Default")
      (node (ref "U6") (pin "161") (pinfunction "CAM1_DN0_161") (pintype "bidirectional"))
    )
    (net (code "212") (name "unconnected-(U6-CAM1_DN1-Pad155)") (class "Default")
      (node (ref "U6") (pin "155") (pinfunction "CAM1_DN1_155") (pintype "bidirectional"))
    )
    (net (code "213") (name "unconnected-(U6-CAM1_DN2-Pad143)") (class "Default")
      (node (ref "U6") (pin "143") (pinfunction "CAM1_DN2_143") (pintype "bidirectional"))
    )
    (net (code "214") (name "unconnected-(U6-CAM1_DN3-Pad137)") (class "Default")
      (node (ref "U6") (pin "137") (pinfunction "CAM1_DN3_137") (pintype "bidirectional"))
    )
    (net (code "215") (name "unconnected-(U6-CAM1_DP0-Pad159)") (class "Default")
      (node (ref "U6") (pin "159") (pinfunction "CAM1_DP0_159") (pintype "bidirectional"))
    )
    (net (code "216") (name "unconnected-(U6-CAM1_DP1-Pad153)") (class "Default")
      (node (ref "U6") (pin "153") (pinfunction "CAM1_DP1_153") (pintype "bidirectional"))
    )
    (net (code "217") (name "unconnected-(U6-CAM1_DP2-Pad141)") (class "Default")
      (node (ref "U6") (pin "141") (pinfunction "CAM1_DP2_141") (pintype "bidirectional"))
    )
    (net (code "218") (name "unconnected-(U6-CAM1_DP3-Pad135)") (class "Default")
      (node (ref "U6") (pin "135") (pinfunction "CAM1_DP3_135") (pintype "bidirectional"))
    )
    (net (code "219") (name "unconnected-(U6-DSI0_CN-Pad105)") (class "Default")
      (node (ref "U6") (pin "105") (pinfunction "DSI0_CN_105") (pintype "bidirectional"))
    )
    (net (code "220") (name "unconnected-(U6-DSI0_CP-Pad107)") (class "Default")
      (node (ref "U6") (pin "107") (pinfunction "DSI0_CP_107") (pintype "bidirectional"))
    )
    (net (code "221") (name "unconnected-(U6-DSI0_DN0-Pad99)") (class "Default")
      (node (ref "U6") (pin "99") (pinfunction "DSI0_DN0_99") (pintype "bidirectional"))
    )
    (net (code "222") (name "unconnected-(U6-DSI0_DN1-Pad93)") (class "Default")
      (node (ref "U6") (pin "93") (pinfunction "DSI0_DN1_93") (pintype "bidirectional"))
    )
    (net (code "223") (name "unconnected-(U6-DSI0_DP0-Pad101)") (class "Default")
      (node (ref "U6") (pin "101") (pinfunction "DSI0_DP0_101") (pintype "bidirectional"))
    )
    (net (code "224") (name "unconnected-(U6-DSI0_DP1-Pad95)") (class "Default")
      (node (ref "U6") (pin "95") (pinfunction "DSI0_DP1_95") (pintype "bidirectional"))
    )
    (net (code "225") (name "unconnected-(U6-DSI1_CN-Pad102)") (class "Default")
      (node (ref "U6") (pin "102") (pinfunction "DSI1_CN_102") (pintype "bidirectional"))
    )
    (net (code "226") (name "unconnected-(U6-DSI1_CP-Pad100)") (class "Default")
      (node (ref "U6") (pin "100") (pinfunction "DSI1_CP_100") (pintype "bidirectional"))
    )
    (net (code "227") (name "unconnected-(U6-DSI1_DN0-Pad96)") (class "Default")
      (node (ref "U6") (pin "96") (pinfunction "DSI1_DN0_96") (pintype "bidirectional"))
    )
    (net (code "228") (name "unconnected-(U6-DSI1_DN1-Pad120)") (class "Default")
      (node (ref "U6") (pin "120") (pinfunction "DSI1_DN1_120") (pintype "bidirectional"))
    )
    (net (code "229") (name "unconnected-(U6-DSI1_DN2-Pad114)") (class "Default")
      (node (ref "U6") (pin "114") (pinfunction "DSI1_DN2_114") (pintype "bidirectional"))
    )
    (net (code "230") (name "unconnected-(U6-DSI1_DN3-Pad108)") (class "Default")
      (node (ref "U6") (pin "108") (pinfunction "DSI1_DN3_108") (pintype "bidirectional"))
    )
    (net (code "231") (name "unconnected-(U6-DSI1_DP0-Pad94)") (class "Default")
      (node (ref "U6") (pin "94") (pinfunction "DSI1_DP0_94") (pintype "bidirectional"))
    )
    (net (code "232") (name "unconnected-(U6-DSI1_DP1-Pad118)") (class "Default")
      (node (ref "U6") (pin "118") (pinfunction "DSI1_DP1_118") (pintype "bidirectional"))
    )
    (net (code "233") (name "unconnected-(U6-DSI1_DP2-Pad112)") (class "Default")
      (node (ref "U6") (pin "112") (pinfunction "DSI1_DP2_112") (pintype "bidirectional"))
    )
    (net (code "234") (name "unconnected-(U6-DSI1_DP3-Pad106)") (class "Default")
      (node (ref "U6") (pin "106") (pinfunction "DSI1_DP3_106") (pintype "bidirectional"))
    )
    (net (code "235") (name "unconnected-(U6-GPIO12-Pad45)") (class "Default")
      (node (ref "U6") (pin "45") (pinfunction "GPIO12_45") (pintype "bidirectional"))
    )
    (net (code "236") (name "unconnected-(U6-GPIO13-Pad47)") (class "Default")
      (node (ref "U6") (pin "47") (pinfunction "GPIO13_47") (pintype "bidirectional"))
    )
    (net (code "237") (name "unconnected-(U6-GPIO16-Pad57)") (class "Default")
      (node (ref "U6") (pin "57") (pinfunction "GPIO16_57") (pintype "bidirectional"))
    )
    (net (code "238") (name "unconnected-(U6-GPIO17-Pad59)") (class "Default")
      (node (ref "U6") (pin "59") (pinfunction "GPIO17_59") (pintype "bidirectional"))
    )
    (net (code "239") (name "unconnected-(U6-GPIO29-Pad30)") (class "Default")
      (node (ref "U6") (pin "30") (pinfunction "GPIO29_30") (pintype "bidirectional"))
    )
    (net (code "240") (name "unconnected-(U6-GPIO30-Pad34)") (class "Default")
      (node (ref "U6") (pin "34") (pinfunction "GPIO30_34") (pintype "bidirectional"))
    )
    (net (code "241") (name "unconnected-(U6-GPIO31-Pad36)") (class "Default")
      (node (ref "U6") (pin "36") (pinfunction "GPIO31_36") (pintype "bidirectional"))
    )
    (net (code "242") (name "unconnected-(U6-GPIO34-Pad52)") (class "Default")
      (node (ref "U6") (pin "52") (pinfunction "GPIO34_52") (pintype "bidirectional"))
    )
    (net (code "243") (name "unconnected-(U6-GPIO35-Pad54)") (class "Default")
      (node (ref "U6") (pin "54") (pinfunction "GPIO35_54") (pintype "bidirectional"))
    )
    (net (code "244") (name "unconnected-(U6-GPIO41-Pad72)") (class "Default")
      (node (ref "U6") (pin "72") (pinfunction "GPIO41_72") (pintype "bidirectional"))
    )
    (net (code "245") (name "unconnected-(U6-GPIO45-Pad84)") (class "Default")
      (node (ref "U6") (pin "84") (pinfunction "GPIO45_84") (pintype "bidirectional"))
    )
    (net (code "246") (name "unconnected-(U6-NC-Pad124)") (class "Default")
      (node (ref "U6") (pin "124") (pinfunction "NC_124") (pintype "bidirectional"))
    )
    (net (code "247") (name "unconnected-(U6-NC-Pad126)") (class "Default")
      (node (ref "U6") (pin "126") (pinfunction "NC_126") (pintype "bidirectional"))
    )
    (net (code "248") (name "unconnected-(U6-NC-Pad128)") (class "Default")
      (node (ref "U6") (pin "128") (pinfunction "NC_128") (pintype "bidirectional"))
    )
    (net (code "249") (name "unconnected-(U6-NC-Pad130)") (class "Default")
      (node (ref "U6") (pin "130") (pinfunction "NC_130") (pintype "bidirectional"))
    )
    (net (code "250") (name "unconnected-(U6-NC-Pad132)") (class "Default")
      (node (ref "U6") (pin "132") (pinfunction "NC_132") (pintype "bidirectional"))
    )
    (net (code "251") (name "unconnected-(U6-NC-Pad154)") (class "Default")
      (node (ref "U6") (pin "154") (pinfunction "NC_154") (pintype "bidirectional"))
    )
    (net (code "252") (name "unconnected-(U6-NC-Pad156)") (class "Default")
      (node (ref "U6") (pin "156") (pinfunction "NC_156") (pintype "bidirectional"))
    )
    (net (code "253") (name "unconnected-(U6-NC-Pad158)") (class "Default")
      (node (ref "U6") (pin "158") (pinfunction "NC_158") (pintype "bidirectional"))
    )
    (net (code "254") (name "unconnected-(U6-NC-Pad160)") (class "Default")
      (node (ref "U6") (pin "160") (pinfunction "NC_160") (pintype "bidirectional"))
    )
    (net (code "255") (name "unconnected-(U6-NC-Pad162)") (class "Default")
      (node (ref "U6") (pin "162") (pinfunction "NC_162") (pintype "bidirectional"))
    )
    (net (code "256") (name "unconnected-(U6-RUN-Pad177)") (class "Default")
      (node (ref "U6") (pin "177") (pinfunction "RUN_177") (pintype "bidirectional"))
    )
    (net (code "257") (name "unconnected-(U6-TVDAC-Pad166)") (class "Default")
      (node (ref "U6") (pin "166") (pinfunction "TVDAC_166") (pintype "bidirectional"))
    )
    (net (code "258") (name "unconnected-(U6-VC_TCK-Pad180)") (class "Default")
      (node (ref "U6") (pin "180") (pinfunction "VC_TCK_180") (pintype "bidirectional"))
    )
    (net (code "259") (name "unconnected-(U6-VC_TDI-Pad174)") (class "Default")
      (node (ref "U6") (pin "174") (pinfunction "VC_TDI_174") (pintype "bidirectional"))
    )
    (net (code "260") (name "unconnected-(U6-VC_TDO-Pad178)") (class "Default")
      (node (ref "U6") (pin "178") (pinfunction "VC_TDO_178") (pintype "bidirectional"))
    )
    (net (code "261") (name "unconnected-(U6-VC_TMS-Pad176)") (class "Default")
      (node (ref "U6") (pin "176") (pinfunction "VC_TMS_176") (pintype "bidirectional"))
    )
    (net (code "262") (name "unconnected-(U6-VC_TRST_N-Pad172)") (class "Default")
      (node (ref "U6") (pin "172") (pinfunction "VC_TRST_N_172") (pintype "bidirectional"))
    )
    (net (code "263") (name "unconnected-(U6-VDD_CORE-Pad179)") (class "Default")
      (node (ref "U6") (pin "179") (pinfunction "VDD_CORE_179") (pintype "bidirectional"))
    )
    (net (code "264") (name "unconnected-(U10-PG-Pad4)") (class "Default")
      (node (ref "U10") (pin "4") (pinfunction "PG_4") (pintype "bidirectional"))
    )
    (net (code "265") (name "unconnected-(U11-FLAG3-Pad4)") (class "Default")
      (node (ref "U11") (pin "4") (pinfunction "FLAG3_4") (pintype "passive"))
    )
    (net (code "266") (name "unconnected-(U12-NC-Pad3)") (class "Default")
      (node (ref "U12") (pin "3") (pinfunction "NC_3") (pintype "no_connect"))
    )
    (net (code "267") (name "unconnected-(U12-NC_2-Pad4)") (class "Default")
      (node (ref "U12") (pin "4") (pinfunction "NC_2_4") (pintype "no_connect"))
    )
    (net (code "268") (name "unconnected-(U12-NC_3-Pad5)") (class "Default")
      (node (ref "U12") (pin "5") (pinfunction "NC_3_5") (pintype "bidirectional"))
    )
    (net (code "269") (name "unconnected-(U16-NC-Pad3)") (class "Default")
      (node (ref "U16") (pin "3") (pinfunction "NC_3") (pintype "bidirectional"))
    )
    (net (code "270") (name "unconnected-(U18-PadADC)") (class "Default")
      (node (ref "U18") (pin "ADC") (pinfunction "ADC_ADC") (pintype "bidirectional"))
    )
    (net (code "271") (name "unconnected-(U18-PadGPIO0)") (class "Default")
      (node (ref "U18") (pin "GPIO0") (pinfunction "GPIO0_GPIO0") (pintype "bidirectional"))
    )
    (net (code "272") (name "unconnected-(U18-PadGPIO2)") (class "Default")
      (node (ref "U18") (pin "GPIO2") (pinfunction "GPIO2_GPIO2") (pintype "bidirectional"))
    )
    (net (code "273") (name "unconnected-(U18-PadGPIO4)") (class "Default")
      (node (ref "U18") (pin "GPIO4") (pinfunction "GPIO4_GPIO4") (pintype "bidirectional"))
    )
    (net (code "274") (name "unconnected-(U18-PadGPIO5)") (class "Default")
      (node (ref "U18") (pin "GPIO5") (pinfunction "GPIO5_GPIO5") (pintype "bidirectional"))
    )
    (net (code "275") (name "unconnected-(U18-PadGPIO12)") (class "Default")
      (node (ref "U18") (pin "GPIO12") (pinfunction "GPIO12_GPIO12") (pintype "bidirectional"))
    )
    (net (code "276") (name "unconnected-(U18-PadGPIO13)") (class "Default")
      (node (ref "U18") (pin "GPIO13") (pinfunction "GPIO13_GPIO13") (pintype "bidirectional"))
    )
    (net (code "277") (name "unconnected-(U18-PadGPIO14)") (class "Default")
      (node (ref "U18") (pin "GPIO14") (pinfunction "GPIO14_GPIO14") (pintype "bidirectional"))
    )
    (net (code "278") (name "unconnected-(U18-PadGPIO15)") (class "Default")
      (node (ref "U18") (pin "GPIO15") (pinfunction "GPIO15_GPIO15") (pintype "bidirectional"))
    )
    (net (code "279") (name "unconnected-(U18-PadRESET)") (class "Default")
      (node (ref "U18") (pin "RESET") (pinfunction "RESET_RESET") (pintype "bidirectional"))
    )
    (net (code "280") (name "unconnected-(U18-RX-PadRXD0)") (class "Default")
      (node (ref "U18") (pin "RXD0") (pinfunction "RX_RXD0") (pintype "bidirectional"))
    )
    (net (code "281") (name "unconnected-(U18-TX-PadTXD0)") (class "Default")
      (node (ref "U18") (pin "TXD0") (pinfunction "TX_TXD0") (pintype "bidirectional"))
    )
    (net (code "282") (name "unconnected-(U19-HP_L-Pad31)") (class "Default")
      (node (ref "U19") (pin "31") (pinfunction "HP_L_31") (pintype "bidirectional"))
    )
    (net (code "283") (name "unconnected-(U19-HP_R-Pad29)") (class "Default")
      (node (ref "U19") (pin "29") (pinfunction "HP_R_29") (pintype "bidirectional"))
    )
    (net (code "284") (name "unconnected-(U19-LIN2-Pad3)") (class "Default")
      (node (ref "U19") (pin "3") (pinfunction "LIN2_3") (pintype "bidirectional"))
    )
    (net (code "285") (name "unconnected-(U19-LIN3-Pad2)") (class "Default")
      (node (ref "U19") (pin "2") (pinfunction "LIN3_2") (pintype "bidirectional"))
    )
    (net (code "286") (name "unconnected-(U19-MICBIAS-Pad1)") (class "Default")
      (node (ref "U19") (pin "1") (pinfunction "MICBIAS_1") (pintype "bidirectional"))
    )
    (net (code "287") (name "unconnected-(U19-OUT3-Pad30)") (class "Default")
      (node (ref "U19") (pin "30") (pinfunction "OUT3_30") (pintype "bidirectional"))
    )
    (net (code "288") (name "unconnected-(U19-RIN2-Pad6)") (class "Default")
      (node (ref "U19") (pin "6") (pinfunction "RIN2_6") (pintype "bidirectional"))
    )
    (net (code "289") (name "unconnected-(U19-RIN3-Pad7)") (class "Default")
      (node (ref "U19") (pin "7") (pinfunction "RIN3_7") (pintype "bidirectional"))
    )
    (net (code "290") (name "unconnected-(U19-SPK_LN-Pad23)") (class "Default")
      (node (ref "U19") (pin "23") (pinfunction "SPK_LN_23") (pintype "bidirectional"))
    )
    (net (code "291") (name "unconnected-(U19-SPK_LP-Pad25)") (class "Default")
      (node (ref "U19") (pin "25") (pinfunction "SPK_LP_25") (pintype "bidirectional"))
    )
  )
)
